# Loongson_Continuation.net
KiCad netlist of a schematic drawn in EasyEDA Pro
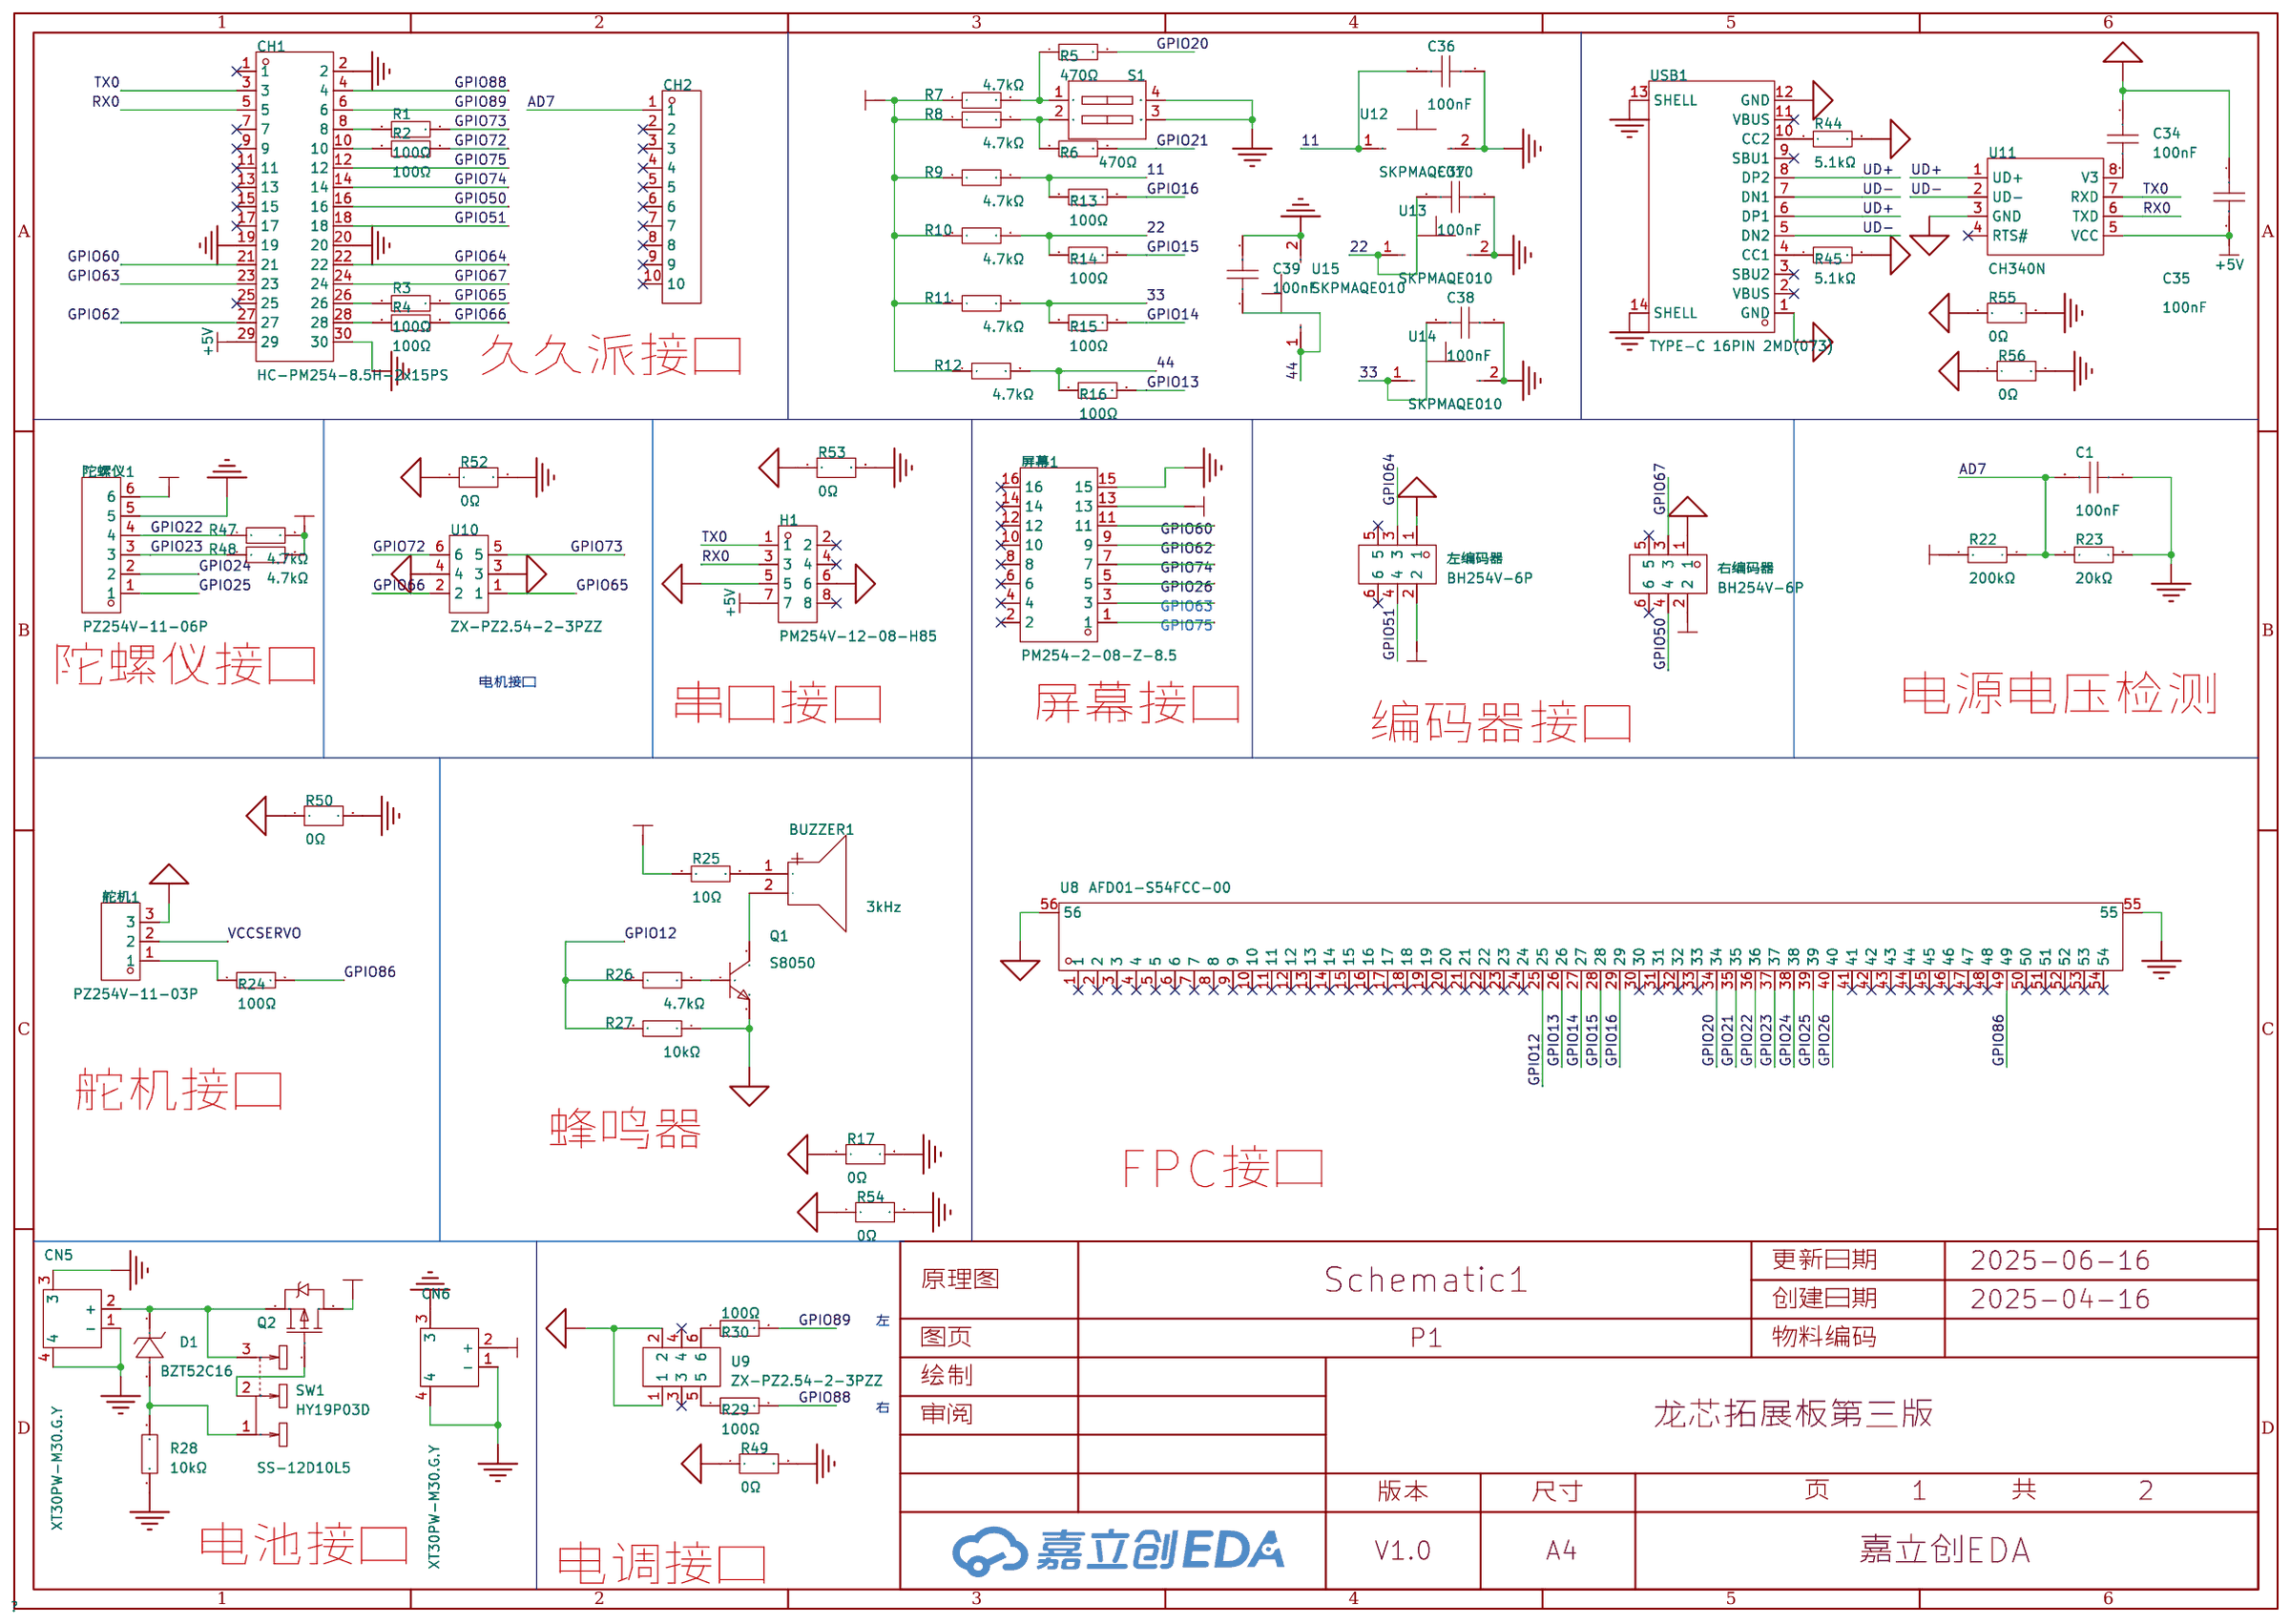
[diagram p0: P1]
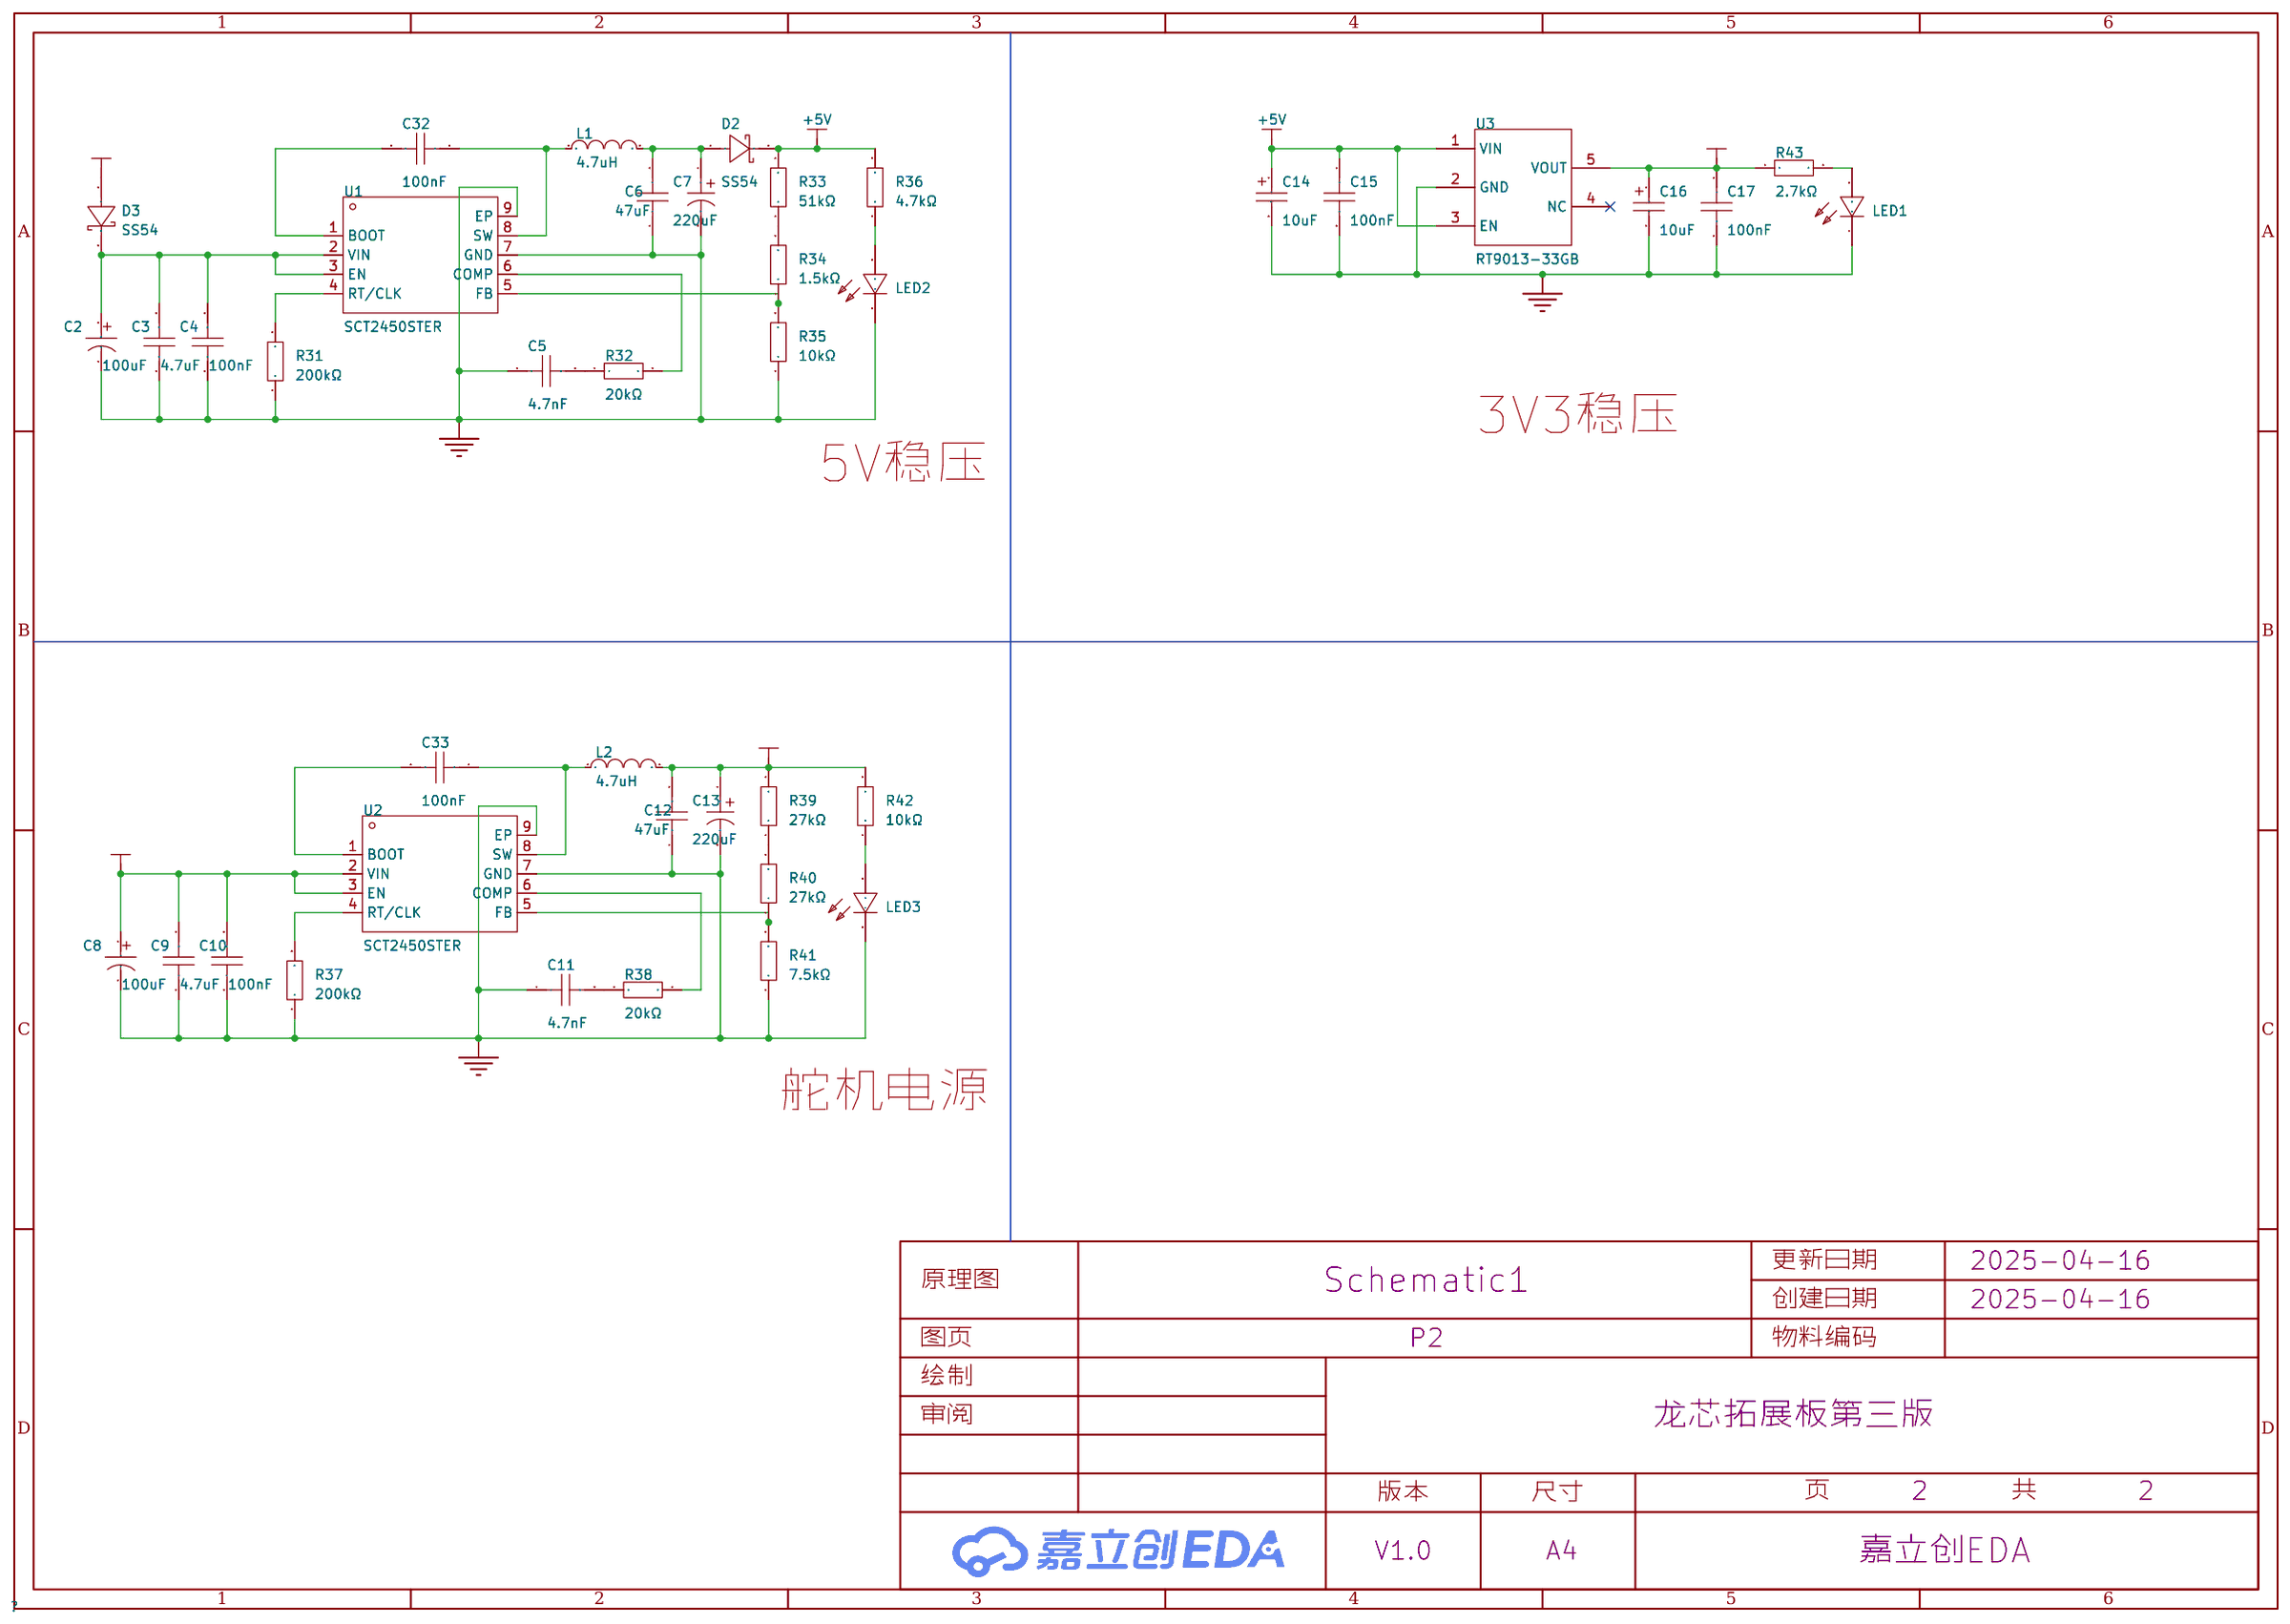
[diagram p1: P2]

(export (version "E")
  (design (tool "Eeschema 10.0.6"))
  (components
    (comp (ref "BUZZER1")
      (value "3kHz")
      (footprint "easyedapro:BUZ-TH_BD9.0-P5.00-D0.6-FD")
      (description "驱动方式:有源(内含驱动线路);构造类型:电磁式;频率:3kHz;声压(SPL):85dB;")
      (fields (field (name "Manufacturer Part") "HNB09A03") (field (name "Manufacturer") "华能"))
      (libsource (lib "easyedapro") (part "HNB09A03"))
    )
    (comp (ref "C1")
      (value "100nF")
      (footprint "easyedapro:C0603")
      (description "容值:100nF;精度:±10%;额定电压:50V;材质(温度系数):X7R;")
      (fields
        (field (name "Manufacturer Part") "CGA0603X7R104K500JT")
        (field (name "Manufacturer") "HRE(芯声)")
      )
      (libsource (lib "easyedapro") (part "CGA0603X7R104K500JT"))
    )
    (comp (ref "C34")
      (value "100nF")
      (footprint "easyedapro:C0603")
      (description "容值:100nF;精度:±10%;额定电压:50V;材质(温度系数):X7R;")
      (fields
        (field (name "Manufacturer Part") "CGA0603X7R104K500JT")
        (field (name "Manufacturer") "HRE(芯声)")
      )
      (libsource (lib "easyedapro") (part "CGA0603X7R104K500JT"))
    )
    (comp (ref "C35")
      (value "100nF")
      (footprint "easyedapro:C0603")
      (description "容值:100nF;精度:±10%;额定电压:50V;材质(温度系数):X7R;")
      (fields
        (field (name "Manufacturer Part") "CGA0603X7R104K500JT")
        (field (name "Manufacturer") "HRE(芯声)")
      )
      (libsource (lib "easyedapro") (part "CGA0603X7R104K500JT"))
    )
    (comp (ref "C36")
      (value "100nF")
      (footprint "easyedapro:C0603")
      (description "容值:100nF;精度:±10%;额定电压:50V;材质(温度系数):X7R;")
      (fields
        (field (name "Manufacturer Part") "CGA0603X7R104K500JT")
        (field (name "Manufacturer") "HRE(芯声)")
      )
      (libsource (lib "easyedapro") (part "CGA0603X7R104K500JT"))
    )
    (comp (ref "C37")
      (value "100nF")
      (footprint "easyedapro:C0603")
      (description "容值:100nF;精度:±10%;额定电压:50V;材质(温度系数):X7R;")
      (fields
        (field (name "Manufacturer Part") "CGA0603X7R104K500JT")
        (field (name "Manufacturer") "HRE(芯声)")
      )
      (libsource (lib "easyedapro") (part "CGA0603X7R104K500JT"))
    )
    (comp (ref "C38")
      (value "100nF")
      (footprint "easyedapro:C0603")
      (description "容值:100nF;精度:±10%;额定电压:50V;材质(温度系数):X7R;")
      (fields
        (field (name "Manufacturer Part") "CGA0603X7R104K500JT")
        (field (name "Manufacturer") "HRE(芯声)")
      )
      (libsource (lib "easyedapro") (part "CGA0603X7R104K500JT"))
    )
    (comp (ref "C39")
      (value "100nF")
      (footprint "easyedapro:C0603")
      (description "容值:100nF;精度:±10%;额定电压:50V;材质(温度系数):X7R;")
      (fields
        (field (name "Manufacturer Part") "CGA0603X7R104K500JT")
        (field (name "Manufacturer") "HRE(芯声)")
      )
      (libsource (lib "easyedapro") (part "CGA0603X7R104K500JT"))
    )
    (comp (ref "CH1")
      (value "HC-PM254-8.5H-2x15PS")
      (footprint "easyedapro:HDR-SMD_30P-P2.54-V-F-R2-C15-LS7.1-1")
      (fields (field (name "Manufacturer") "HC(虹成电子)"))
      (libsource (lib "easyedapro") (part "HC-PM254-8.5H-2X15PS"))
    )
    (comp (ref "CH2")
      (value "HX PM2.54-1x10P TP-YQ")
      (footprint "easyedapro:HDR-SMD_10P-P2.54-V-F-LS4.7_R2")
      (fields (field (name "Manufacturer") "hanxia(韩下)"))
      (libsource (lib "easyedapro") (part "HX PM2.54-1X10P TP-YQ"))
    )
    (comp (ref "CN5")
      (value "XT30PW-M30.G.Y")
      (footprint "easyedapro:CONN-TH_XT30PW-M")
      (description "类别:-;类型1:-;")
      (fields (field (name "Manufacturer") "AMASS(艾迈斯)"))
      (libsource (lib "easyedapro") (part "XT30PW-M"))
    )
    (comp (ref "CN6")
      (value "XT30PW-M30.G.Y")
      (footprint "easyedapro:CONN-TH_XT30PW-M")
      (description "类别:-;类型1:-;")
      (fields (field (name "Manufacturer") "AMASS(艾迈斯)"))
      (libsource (lib "easyedapro") (part "XT30PW-M"))
    )
    (comp (ref "D1")
      (value "BZT52C16")
      (footprint "easyedapro:SOD-123_L2.7-W1.6-LS3.7-RD")
      (description "二极管配置:独立式;稳压值(标称值):16V;稳压值(范围):15.2V~16.8V;耗散功率(Pd):500mW;")
      (fields (field (name "Manufacturer") "宏嘉诚"))
      (libsource (lib "easyedapro") (part "BZT52C16_C19077413"))
    )
    (comp (ref "H1")
      (value "PM254V-12-08-H85")
      (footprint "easyedapro:HDR-TH_8P-P2.54-V-F-R2-C4-S2.54")
      (fields (field (name "Manufacturer") "XFCN(兴飞)"))
      (libsource (lib "easyedapro") (part "PM254V-12-08-H85_C2834799"))
    )
    (comp (ref "Q1")
      (value "S8050")
      (footprint "easyedapro:SOT-23-3_L2.9-W1.6-P1.90-LS2.8-BR")
      (description "晶体管类型:NPN;集电极电流(Ic):500mA;集射极击穿电压(Vceo):25V;功率(Pd):300mW;")
      (fields (field (name "Manufacturer") "Hottech(合科泰)"))
      (libsource (lib "easyedapro") (part "S8050_C181158"))
    )
    (comp (ref "Q2")
      (value "HY19P03D")
      (footprint "easyedapro:TO-252-2_L6.6-W6.1-P4.57-LS9.9-TL-CW")
      (fields (field (name "Manufacturer") "HUAYI(华羿微)"))
      (libsource (lib "easyedapro") (part "HY19P03D"))
    )
    (comp (ref "R1")
      (value "100Ω")
      (footprint "easyedapro:R0603")
      (description "电阻类型:厚膜电阻;阻值:100Ω;精度:±1%;功率:100mW;最大工作电压:75V;温度系数:±200ppm/°C;")
      (fields
        (field (name "Manufacturer Part") "0603WAF1000T5E")
        (field (name "Manufacturer") "UNI-ROYAL(厚声)")
      )
      (libsource (lib "easyedapro") (part "0603WAF1000T5E"))
    )
    (comp (ref "R2")
      (value "100Ω")
      (footprint "easyedapro:R0603")
      (description "电阻类型:厚膜电阻;阻值:100Ω;精度:±1%;功率:100mW;最大工作电压:75V;温度系数:±200ppm/°C;")
      (fields
        (field (name "Manufacturer Part") "0603WAF1000T5E")
        (field (name "Manufacturer") "UNI-ROYAL(厚声)")
      )
      (libsource (lib "easyedapro") (part "0603WAF1000T5E"))
    )
    (comp (ref "R3")
      (value "100Ω")
      (footprint "easyedapro:R0603")
      (description "电阻类型:厚膜电阻;阻值:100Ω;精度:±1%;功率:100mW;最大工作电压:75V;温度系数:±200ppm/°C;")
      (fields
        (field (name "Manufacturer Part") "0603WAF1000T5E")
        (field (name "Manufacturer") "UNI-ROYAL(厚声)")
      )
      (libsource (lib "easyedapro") (part "0603WAF1000T5E"))
    )
    (comp (ref "R4")
      (value "100Ω")
      (footprint "easyedapro:R0603")
      (description "电阻类型:厚膜电阻;阻值:100Ω;精度:±1%;功率:100mW;最大工作电压:75V;温度系数:±200ppm/°C;")
      (fields
        (field (name "Manufacturer Part") "0603WAF1000T5E")
        (field (name "Manufacturer") "UNI-ROYAL(厚声)")
      )
      (libsource (lib "easyedapro") (part "0603WAF1000T5E"))
    )
    (comp (ref "R5")
      (value "470Ω")
      (footprint "easyedapro:R0603")
      (description "电阻类型:厚膜电阻;阻值:470Ω;精度:±1%;功率:100mW;最大工作电压:75V;温度系数:±100ppm/°C;")
      (fields
        (field (name "Manufacturer Part") "0603WAF4700T5E")
        (field (name "Manufacturer") "UNI-ROYAL(厚声)")
      )
      (libsource (lib "easyedapro") (part "0603WAF4700T5E"))
    )
    (comp (ref "R6")
      (value "470Ω")
      (footprint "easyedapro:R0603")
      (description "电阻类型:厚膜电阻;阻值:470Ω;精度:±1%;功率:100mW;最大工作电压:75V;温度系数:±100ppm/°C;")
      (fields
        (field (name "Manufacturer Part") "0603WAF4700T5E")
        (field (name "Manufacturer") "UNI-ROYAL(厚声)")
      )
      (libsource (lib "easyedapro") (part "0603WAF4700T5E"))
    )
    (comp (ref "R7")
      (value "4.7kΩ")
      (footprint "easyedapro:R0603")
      (description "电阻类型:厚膜电阻;阻值:4.7kΩ;精度:±1%;功率:100mW;最大工作电压:75V;温度系数:±100ppm/°C;")
      (fields
        (field (name "Manufacturer Part") "0603WAF4701T5E")
        (field (name "Manufacturer") "UNI-ROYAL(厚声)")
      )
      (libsource (lib "easyedapro") (part "0603WAF4701T5E"))
    )
    (comp (ref "R8")
      (value "4.7kΩ")
      (footprint "easyedapro:R0603")
      (description "电阻类型:厚膜电阻;阻值:4.7kΩ;精度:±1%;功率:100mW;最大工作电压:75V;温度系数:±100ppm/°C;")
      (fields
        (field (name "Manufacturer Part") "0603WAF4701T5E")
        (field (name "Manufacturer") "UNI-ROYAL(厚声)")
      )
      (libsource (lib "easyedapro") (part "0603WAF4701T5E"))
    )
    (comp (ref "R9")
      (value "4.7kΩ")
      (footprint "easyedapro:R0603")
      (description "电阻类型:厚膜电阻;阻值:4.7kΩ;精度:±1%;功率:100mW;最大工作电压:75V;温度系数:±100ppm/°C;")
      (fields
        (field (name "Manufacturer Part") "0603WAF4701T5E")
        (field (name "Manufacturer") "UNI-ROYAL(厚声)")
      )
      (libsource (lib "easyedapro") (part "0603WAF4701T5E"))
    )
    (comp (ref "R10")
      (value "4.7kΩ")
      (footprint "easyedapro:R0603")
      (description "电阻类型:厚膜电阻;阻值:4.7kΩ;精度:±1%;功率:100mW;最大工作电压:75V;温度系数:±100ppm/°C;")
      (fields
        (field (name "Manufacturer Part") "0603WAF4701T5E")
        (field (name "Manufacturer") "UNI-ROYAL(厚声)")
      )
      (libsource (lib "easyedapro") (part "0603WAF4701T5E"))
    )
    (comp (ref "R11")
      (value "4.7kΩ")
      (footprint "easyedapro:R0603")
      (description "电阻类型:厚膜电阻;阻值:4.7kΩ;精度:±1%;功率:100mW;最大工作电压:75V;温度系数:±100ppm/°C;")
      (fields
        (field (name "Manufacturer Part") "0603WAF4701T5E")
        (field (name "Manufacturer") "UNI-ROYAL(厚声)")
      )
      (libsource (lib "easyedapro") (part "0603WAF4701T5E"))
    )
    (comp (ref "R12")
      (value "4.7kΩ")
      (footprint "easyedapro:R0603")
      (description "电阻类型:厚膜电阻;阻值:4.7kΩ;精度:±1%;功率:100mW;最大工作电压:75V;温度系数:±100ppm/°C;")
      (fields
        (field (name "Manufacturer Part") "0603WAF4701T5E")
        (field (name "Manufacturer") "UNI-ROYAL(厚声)")
      )
      (libsource (lib "easyedapro") (part "0603WAF4701T5E"))
    )
    (comp (ref "R13")
      (value "100Ω")
      (footprint "easyedapro:R0603")
      (description "电阻类型:厚膜电阻;阻值:100Ω;精度:±1%;功率:100mW;最大工作电压:75V;温度系数:±200ppm/°C;")
      (fields
        (field (name "Manufacturer Part") "0603WAF1000T5E")
        (field (name "Manufacturer") "UNI-ROYAL(厚声)")
      )
      (libsource (lib "easyedapro") (part "0603WAF1000T5E"))
    )
    (comp (ref "R14")
      (value "100Ω")
      (footprint "easyedapro:R0603")
      (description "电阻类型:厚膜电阻;阻值:100Ω;精度:±1%;功率:100mW;最大工作电压:75V;温度系数:±200ppm/°C;")
      (fields
        (field (name "Manufacturer Part") "0603WAF1000T5E")
        (field (name "Manufacturer") "UNI-ROYAL(厚声)")
      )
      (libsource (lib "easyedapro") (part "0603WAF1000T5E"))
    )
    (comp (ref "R15")
      (value "100Ω")
      (footprint "easyedapro:R0603")
      (description "电阻类型:厚膜电阻;阻值:100Ω;精度:±1%;功率:100mW;最大工作电压:75V;温度系数:±200ppm/°C;")
      (fields
        (field (name "Manufacturer Part") "0603WAF1000T5E")
        (field (name "Manufacturer") "UNI-ROYAL(厚声)")
      )
      (libsource (lib "easyedapro") (part "0603WAF1000T5E"))
    )
    (comp (ref "R16")
      (value "100Ω")
      (footprint "easyedapro:R0603")
      (description "电阻类型:厚膜电阻;阻值:100Ω;精度:±1%;功率:100mW;最大工作电压:75V;温度系数:±200ppm/°C;")
      (fields
        (field (name "Manufacturer Part") "0603WAF1000T5E")
        (field (name "Manufacturer") "UNI-ROYAL(厚声)")
      )
      (libsource (lib "easyedapro") (part "0603WAF1000T5E"))
    )
    (comp (ref "R17")
      (value "0Ω")
      (footprint "easyedapro:R1206")
      (description "电阻类型:厚膜电阻;阻值:0Ω;精度:±5%;功率:250mW;最大工作电压:200V;")
      (fields (field (name "Manufacturer Part") "FRC1206P000 TS") (field (name "Manufacturer") "FOJAN(富捷)"))
      (libsource (lib "easyedapro") (part "FRC1206P000 TS"))
    )
    (comp (ref "R22")
      (value "200kΩ")
      (footprint "easyedapro:R0603")
      (description "电阻类型:厚膜电阻;阻值:200kΩ;精度:±1%;功率:100mW;最大工作电压:75V;温度系数:±100ppm/°C;")
      (fields
        (field (name "Manufacturer Part") "0603WAF2003T5E")
        (field (name "Manufacturer") "UNI-ROYAL(厚声)")
      )
      (libsource (lib "easyedapro") (part "0603WAF2003T5E"))
    )
    (comp (ref "R23")
      (value "20kΩ")
      (footprint "easyedapro:R0603")
      (description "电阻类型:厚膜电阻;阻值:20kΩ;精度:±1%;功率:100mW;最大工作电压:75V;温度系数:±100ppm/°C;")
      (fields
        (field (name "Manufacturer Part") "0603WAF2002T5E")
        (field (name "Manufacturer") "UNI-ROYAL(厚声)")
      )
      (libsource (lib "easyedapro") (part "0603WAF2002T5E"))
    )
    (comp (ref "R24")
      (value "100Ω")
      (footprint "easyedapro:R0603")
      (description "电阻类型:厚膜电阻;阻值:100Ω;精度:±1%;功率:100mW;最大工作电压:75V;温度系数:±200ppm/°C;")
      (fields
        (field (name "Manufacturer Part") "0603WAF1000T5E")
        (field (name "Manufacturer") "UNI-ROYAL(厚声)")
      )
      (libsource (lib "easyedapro") (part "0603WAF1000T5E"))
    )
    (comp (ref "R25")
      (value "10Ω")
      (footprint "easyedapro:R0603")
      (description "电阻类型:厚膜电阻;阻值:10Ω;精度:±1%;功率:100mW;最大工作电压:75V;温度系数:±400ppm/°C;")
      (fields
        (field (name "Manufacturer Part") "0603WAF100JT5E")
        (field (name "Manufacturer") "UNI-ROYAL(厚声)")
      )
      (libsource (lib "easyedapro") (part "0603WAF100JT5E"))
    )
    (comp (ref "R26")
      (value "4.7kΩ")
      (footprint "easyedapro:R0603")
      (description "电阻类型:厚膜电阻;阻值:4.7kΩ;精度:±1%;功率:100mW;最大工作电压:75V;温度系数:±100ppm/°C;")
      (fields
        (field (name "Manufacturer Part") "0603WAF4701T5E")
        (field (name "Manufacturer") "UNI-ROYAL(厚声)")
      )
      (libsource (lib "easyedapro") (part "0603WAF4701T5E"))
    )
    (comp (ref "R27")
      (value "10kΩ")
      (footprint "easyedapro:R0603")
      (description "电阻类型:厚膜电阻;阻值:10kΩ;精度:±1%;功率:100mW;最大工作电压:75V;温度系数:±100ppm/°C;")
      (fields
        (field (name "Manufacturer Part") "0603WAF1002T5E")
        (field (name "Manufacturer") "UNI-ROYAL(厚声)")
      )
      (libsource (lib "easyedapro") (part "0603WAF1002T5E"))
    )
    (comp (ref "R28")
      (value "10kΩ")
      (footprint "easyedapro:R0603")
      (description "电阻类型:厚膜电阻;阻值:10kΩ;精度:±1%;功率:100mW;最大工作电压:75V;温度系数:±100ppm/°C;")
      (fields
        (field (name "Manufacturer Part") "0603WAF1002T5E")
        (field (name "Manufacturer") "UNI-ROYAL(厚声)")
      )
      (libsource (lib "easyedapro") (part "0603WAF1002T5E"))
    )
    (comp (ref "R29")
      (value "100Ω")
      (footprint "easyedapro:R0603")
      (description "电阻类型:厚膜电阻;阻值:100Ω;精度:±1%;功率:100mW;最大工作电压:75V;温度系数:±200ppm/°C;")
      (fields
        (field (name "Manufacturer Part") "0603WAF1000T5E")
        (field (name "Manufacturer") "UNI-ROYAL(厚声)")
      )
      (libsource (lib "easyedapro") (part "0603WAF1000T5E"))
    )
    (comp (ref "R30")
      (value "100Ω")
      (footprint "easyedapro:R0603")
      (description "电阻类型:厚膜电阻;阻值:100Ω;精度:±1%;功率:100mW;最大工作电压:75V;温度系数:±200ppm/°C;")
      (fields
        (field (name "Manufacturer Part") "0603WAF1000T5E")
        (field (name "Manufacturer") "UNI-ROYAL(厚声)")
      )
      (libsource (lib "easyedapro") (part "0603WAF1000T5E"))
    )
    (comp (ref "R44")
      (value "5.1kΩ")
      (footprint "easyedapro:R0603")
      (description "电阻类型:厚膜电阻;阻值:5.1kΩ;精度:±1%;功率:100mW;最大工作电压:75V;温度系数:±100ppm/°C;")
      (fields
        (field (name "Manufacturer Part") "0603WAF5101T5E")
        (field (name "Manufacturer") "UNI-ROYAL(厚声)")
      )
      (libsource (lib "easyedapro") (part "0603WAF5101T5E"))
    )
    (comp (ref "R45")
      (value "5.1kΩ")
      (footprint "easyedapro:R0603")
      (description "电阻类型:厚膜电阻;阻值:5.1kΩ;精度:±1%;功率:100mW;最大工作电压:75V;温度系数:±100ppm/°C;")
      (fields
        (field (name "Manufacturer Part") "0603WAF5101T5E")
        (field (name "Manufacturer") "UNI-ROYAL(厚声)")
      )
      (libsource (lib "easyedapro") (part "0603WAF5101T5E"))
    )
    (comp (ref "R47")
      (value "4.7kΩ")
      (footprint "easyedapro:R0603")
      (description "电阻类型:厚膜电阻;阻值:4.7kΩ;精度:±1%;功率:100mW;最大工作电压:75V;温度系数:±100ppm/°C;")
      (fields
        (field (name "Manufacturer Part") "0603WAF4701T5E")
        (field (name "Manufacturer") "UNI-ROYAL(厚声)")
      )
      (libsource (lib "easyedapro") (part "0603WAF4701T5E"))
    )
    (comp (ref "R48")
      (value "4.7kΩ")
      (footprint "easyedapro:R0603")
      (description "电阻类型:厚膜电阻;阻值:4.7kΩ;精度:±1%;功率:100mW;最大工作电压:75V;温度系数:±100ppm/°C;")
      (fields
        (field (name "Manufacturer Part") "0603WAF4701T5E")
        (field (name "Manufacturer") "UNI-ROYAL(厚声)")
      )
      (libsource (lib "easyedapro") (part "0603WAF4701T5E"))
    )
    (comp (ref "R49")
      (value "0Ω")
      (footprint "easyedapro:R1206")
      (description "电阻类型:厚膜电阻;阻值:0Ω;精度:±5%;功率:250mW;最大工作电压:200V;")
      (fields (field (name "Manufacturer Part") "FRC1206P000 TS") (field (name "Manufacturer") "FOJAN(富捷)"))
      (libsource (lib "easyedapro") (part "FRC1206P000 TS"))
    )
    (comp (ref "R50")
      (value "0Ω")
      (footprint "easyedapro:R1206")
      (description "电阻类型:厚膜电阻;阻值:0Ω;精度:±5%;功率:250mW;最大工作电压:200V;")
      (fields (field (name "Manufacturer Part") "FRC1206P000 TS") (field (name "Manufacturer") "FOJAN(富捷)"))
      (libsource (lib "easyedapro") (part "FRC1206P000 TS"))
    )
    (comp (ref "R52")
      (value "0Ω")
      (footprint "easyedapro:R1206")
      (description "电阻类型:厚膜电阻;阻值:0Ω;精度:±5%;功率:250mW;最大工作电压:200V;")
      (fields (field (name "Manufacturer Part") "FRC1206P000 TS") (field (name "Manufacturer") "FOJAN(富捷)"))
      (libsource (lib "easyedapro") (part "FRC1206P000 TS"))
    )
    (comp (ref "R53")
      (value "0Ω")
      (footprint "easyedapro:R1206")
      (description "电阻类型:厚膜电阻;阻值:0Ω;精度:±5%;功率:250mW;最大工作电压:200V;")
      (fields (field (name "Manufacturer Part") "FRC1206P000 TS") (field (name "Manufacturer") "FOJAN(富捷)"))
      (libsource (lib "easyedapro") (part "FRC1206P000 TS"))
    )
    (comp (ref "R54")
      (value "0Ω")
      (footprint "easyedapro:R1206")
      (description "电阻类型:厚膜电阻;阻值:0Ω;精度:±5%;功率:250mW;最大工作电压:200V;")
      (fields (field (name "Manufacturer Part") "FRC1206P000 TS") (field (name "Manufacturer") "FOJAN(富捷)"))
      (libsource (lib "easyedapro") (part "FRC1206P000 TS"))
    )
    (comp (ref "R55")
      (value "0Ω")
      (footprint "easyedapro:R1206")
      (description "电阻类型:厚膜电阻;阻值:0Ω;精度:±5%;功率:250mW;最大工作电压:200V;")
      (fields (field (name "Manufacturer Part") "FRC1206P000 TS") (field (name "Manufacturer") "FOJAN(富捷)"))
      (libsource (lib "easyedapro") (part "FRC1206P000 TS"))
    )
    (comp (ref "R56")
      (value "0Ω")
      (footprint "easyedapro:R1206")
      (description "电阻类型:厚膜电阻;阻值:0Ω;精度:±5%;功率:250mW;最大工作电压:200V;")
      (fields (field (name "Manufacturer Part") "FRC1206P000 TS") (field (name "Manufacturer") "FOJAN(富捷)"))
      (libsource (lib "easyedapro") (part "FRC1206P000 TS"))
    )
    (comp (ref "S1")
      (value "DSIC02LS-P")
      (footprint "easyedapro:SW-SMD_4P-L5.1-W6.1-P2.54-LS9.8")
      (description "类型:平拨,凸起式;电路结构:单刀单掷;开关位数:2位;额定电流:25mA;额定电压:24V;使用寿命:3千次;颜色:黑色;")
      (fields (field (name "Manufacturer") "XKB Connectivity(中国星坤)"))
      (libsource (lib "easyedapro") (part "DSIC02LS-P_C489174"))
    )
    (comp (ref "SW1")
      (value "SS-12D10L5")
      (footprint "easyedapro:SW-TH_SS-12D10L5")
      (description "电路结构:单刀双掷;安装方式:直插;开关颜色:黑色;额定电流(DC):3A;额定电压(DC):125V;额定电流(AC):3A;额定电压(AC):125V;机械寿命:1万次;")
      (fields (field (name "Manufacturer") "XKB Connectivity(中国星坤)"))
      (libsource (lib "easyedapro") (part "SS-12D10L5"))
    )
    (comp (ref "U8")
      (value "AFD01-S54FCC-00")
      (footprint "easyedapro:FPC-SMD_54P-P0.50_AFD01-S54FCA-00")
      (description "锁定特性:翻盖式;触点类型:下接;触点数量:54P;间距:0.5mm;安装类型:卧贴;")
      (fields (field (name "Manufacturer") "JS(钜硕电子)"))
      (libsource (lib "easyedapro") (part "AFD01-S54FCC-00"))
    )
    (comp (ref "U9")
      (value "ZX-PZ2.54-2-3PZZ")
      (footprint "easyedapro:HDR-TH_6P-P2.54-V-M-R2-C3-S2.54-1")
      (fields (field (name "Manufacturer") "Megastar(兆星)"))
      (libsource (lib "easyedapro") (part "ZX-PZ2.54-2-3PZZ"))
    )
    (comp (ref "U10")
      (value "ZX-PZ2.54-2-3PZZ")
      (footprint "easyedapro:HDR-TH_6P-P2.54-V-M-R2-C3-S2.54-1")
      (fields (field (name "Manufacturer") "Megastar(兆星)"))
      (libsource (lib "easyedapro") (part "ZX-PZ2.54-2-3PZZ"))
    )
    (comp (ref "U11")
      (value "CH340N")
      (footprint "easyedapro:SOP-8_L4.9-W3.9-P1.27-LS6.0-BL")
      (description "应用功能:USB转串口;接口协议:USB 2.0;通道数:1;数据速率:2Mbps;")
      (fields (field (name "Manufacturer") "WCH(南京沁恒)"))
      (libsource (lib "easyedapro") (part "CH340N_C2977777"))
    )
    (comp (ref "U12")
      (value "SKPMAQE010")
      (footprint "easyedapro:KEY-SMD_2P-L6.0-W6.0-P6.00")
      (fields (field (name "Manufacturer") "ALPSALPINE(阿尔卑斯阿尔派)"))
      (libsource (lib "easyedapro") (part "SKPMAQE010"))
    )
    (comp (ref "U13")
      (value "SKPMAQE010")
      (footprint "easyedapro:KEY-SMD_2P-L6.0-W6.0-P6.00")
      (fields (field (name "Manufacturer") "ALPSALPINE(阿尔卑斯阿尔派)"))
      (libsource (lib "easyedapro") (part "SKPMAQE010"))
    )
    (comp (ref "U14")
      (value "SKPMAQE010")
      (footprint "easyedapro:KEY-SMD_2P-L6.0-W6.0-P6.00")
      (fields (field (name "Manufacturer") "ALPSALPINE(阿尔卑斯阿尔派)"))
      (libsource (lib "easyedapro") (part "SKPMAQE010"))
    )
    (comp (ref "U15")
      (value "SKPMAQE010")
      (footprint "easyedapro:KEY-SMD_2P-L6.0-W6.0-P6.00")
      (fields (field (name "Manufacturer") "ALPSALPINE(阿尔卑斯阿尔派)"))
      (libsource (lib "easyedapro") (part "SKPMAQE010"))
    )
    (comp (ref "USB1")
      (value "TYPE-C 16PIN 2MD(073)")
      (footprint "easyedapro:USB-C-SMD_TYPE-C-6PIN-2MD-073")
      (description "连接器类型:Type-C;标准:USB 3.1;公母:母;安装方式:卧贴;触点数量:16P;端口数量:1;额定电流 - 电源:5A;工作温度范围:-25°C~+85°C;")
      (fields (field (name "Manufacturer") "SHOU HAN(首韩)"))
      (libsource (lib "easyedapro") (part "TYPE-C 16PIN 2MD(073)"))
    )
    (comp (ref "右编码器")
      (value "BH254V-6P")
      (footprint "easyedapro:IDC-TH_6P-P2.54-V-R2-C3-S2.54")
      (description "连接器类型:简牛座;间距:2.54mm;结构:2x3P;额定电流:3A;额定电压:250V;封装形式:直插;行距:2.54mm;排数:2;每排PIN数:3;工作温度范围:-40°C~+105°C;")
      (fields (field (name "Manufacturer") "XFCN(兴飞)"))
      (libsource (lib "easyedapro") (part "BH254V-6P"))
    )
    (comp (ref "屏幕1")
      (value "PM254-2-08-Z-8.5")
      (footprint "easyedapro:HDR-TH_16P-P2.54-V-F-R2-C8-S2.54")
      (fields (field (name "Manufacturer") "HCTL(华灿天禄)"))
      (libsource (lib "easyedapro") (part "PM254-2-08-Z-8.5"))
    )
    (comp (ref "左编码器")
      (value "BH254V-6P")
      (footprint "easyedapro:IDC-TH_6P-P2.54-V-R2-C3-S2.54")
      (description "连接器类型:简牛座;间距:2.54mm;结构:2x3P;额定电流:3A;额定电压:250V;封装形式:直插;行距:2.54mm;排数:2;每排PIN数:3;工作温度范围:-40°C~+105°C;")
      (fields (field (name "Manufacturer") "XFCN(兴飞)"))
      (libsource (lib "easyedapro") (part "BH254V-6P"))
    )
    (comp (ref "舵机1")
      (value "PZ254V-11-03P")
      (footprint "easyedapro:HDR-TH_3P-P2.54-V-M")
      (fields (field (name "Manufacturer") "XFCN(兴飞)"))
      (libsource (lib "easyedapro") (part "PZ254V-11-03P_C2937625"))
    )
    (comp (ref "陀螺仪1")
      (value "PZ254V-11-06P")
      (footprint "easyedapro:HDR-TH_6P-P2.54-V-M")
      (fields (field (name "Manufacturer") "XFCN(兴飞)"))
      (libsource (lib "easyedapro") (part "PZ254V-11-06P"))
    )
    (comp (ref "C2")
      (value "100uF")
      (footprint "easyedapro:CAP-SMD_BD6.3-L6.6-W6.6-LS7.6-FD")
      (description "容值:100uF;精度:±20%;额定电压:35V;纹波电流:69mA@120Hz;等效串联电阻(ESR):-;")
      (fields (field (name "Manufacturer Part") "RVT1V101M0607") (field (name "Manufacturer") "ROQANG(容强)"))
      (libsource (lib "easyedapro") (part "RVT1V101M0607"))
    )
    (comp (ref "C3")
      (value "4.7uF")
      (footprint "easyedapro:C1206")
      (description "容值:4.7uF;精度:±10%;额定电压:35V;材质(温度系数):X5R;")
      (fields
        (field (name "Manufacturer Part") "CGA1206X5R475K350NT")
        (field (name "Manufacturer") "HRE(芯声)")
      )
      (libsource (lib "easyedapro") (part "CGA1206X5R475K350NT"))
    )
    (comp (ref "C4")
      (value "100nF")
      (footprint "easyedapro:C0603")
      (description "容值:100nF;精度:±10%;额定电压:50V;材质(温度系数):X7R;")
      (fields
        (field (name "Manufacturer Part") "CGA0603X7R104K500JT")
        (field (name "Manufacturer") "HRE(芯声)")
      )
      (libsource (lib "easyedapro") (part "CGA0603X7R104K500JT"))
    )
    (comp (ref "C5")
      (value "4.7nF")
      (footprint "easyedapro:C0603")
      (description "容值:4.7nF;精度:±10%;额定电压:50V;材质(温度系数):X7R;")
      (fields
        (field (name "Manufacturer Part") "CGA0603X7R472K500JT")
        (field (name "Manufacturer") "HRE(芯声)")
      )
      (libsource (lib "easyedapro") (part "CGA0603X7R472K500JT"))
    )
    (comp (ref "C6")
      (value "47uF")
      (footprint "easyedapro:C1206")
      (description "容值:47uF;精度:±20%;额定电压:25V;材质(温度系数):X5R;")
      (fields
        (field (name "Manufacturer Part") "CGA1206X5R476M250NT")
        (field (name "Manufacturer") "HRE(芯声)")
      )
      (libsource (lib "easyedapro") (part "CGA1206X5R476M250NT"))
    )
    (comp (ref "C7")
      (value "220uF")
      (footprint "easyedapro:CAP-SMD_BD6.3-L6.6-W6.6-LS7.4-FD")
      (description "容值:220uF;精度:±20%;额定电压:25V;纹波电流:150mA@120Hz;等效串联电阻(ESR):-;")
      (fields (field (name "Manufacturer Part") "RVT1E221M0607") (field (name "Manufacturer") "ROQANG(容强)"))
      (libsource (lib "easyedapro") (part "RVT1E221M0607_C2918361"))
    )
    (comp (ref "C8")
      (value "100uF")
      (footprint "easyedapro:CAP-SMD_BD6.3-L6.6-W6.6-LS7.6-FD")
      (description "容值:100uF;精度:±20%;额定电压:35V;纹波电流:69mA@120Hz;等效串联电阻(ESR):-;")
      (fields (field (name "Manufacturer Part") "RVT1V101M0607") (field (name "Manufacturer") "ROQANG(容强)"))
      (libsource (lib "easyedapro") (part "RVT1V101M0607"))
    )
    (comp (ref "C9")
      (value "4.7uF")
      (footprint "easyedapro:C1206")
      (description "容值:4.7uF;精度:±10%;额定电压:35V;材质(温度系数):X5R;")
      (fields
        (field (name "Manufacturer Part") "CGA1206X5R475K350NT")
        (field (name "Manufacturer") "HRE(芯声)")
      )
      (libsource (lib "easyedapro") (part "CGA1206X5R475K350NT"))
    )
    (comp (ref "C10")
      (value "100nF")
      (footprint "easyedapro:C0603")
      (description "容值:100nF;精度:±10%;额定电压:50V;材质(温度系数):X7R;")
      (fields
        (field (name "Manufacturer Part") "CGA0603X7R104K500JT")
        (field (name "Manufacturer") "HRE(芯声)")
      )
      (libsource (lib "easyedapro") (part "CGA0603X7R104K500JT"))
    )
    (comp (ref "C11")
      (value "4.7nF")
      (footprint "easyedapro:C0603")
      (description "容值:4.7nF;精度:±10%;额定电压:50V;材质(温度系数):X7R;")
      (fields
        (field (name "Manufacturer Part") "CGA0603X7R472K500JT")
        (field (name "Manufacturer") "HRE(芯声)")
      )
      (libsource (lib "easyedapro") (part "CGA0603X7R472K500JT"))
    )
    (comp (ref "C12")
      (value "47uF")
      (footprint "easyedapro:C1206")
      (description "容值:47uF;精度:±20%;额定电压:25V;材质(温度系数):X5R;")
      (fields
        (field (name "Manufacturer Part") "CGA1206X5R476M250NT")
        (field (name "Manufacturer") "HRE(芯声)")
      )
      (libsource (lib "easyedapro") (part "CGA1206X5R476M250NT"))
    )
    (comp (ref "C13")
      (value "220uF")
      (footprint "easyedapro:CAP-SMD_BD6.3-L6.6-W6.6-LS7.4-FD")
      (description "容值:220uF;精度:±20%;额定电压:25V;纹波电流:150mA@120Hz;等效串联电阻(ESR):-;")
      (fields (field (name "Manufacturer Part") "RVT1E221M0607") (field (name "Manufacturer") "ROQANG(容强)"))
      (libsource (lib "easyedapro") (part "RVT1E221M0607_C2918361"))
    )
    (comp (ref "C14")
      (value "10uF")
      (footprint "easyedapro:CAP-SMD_L3.2-W1.6-RD-C7171")
      (description "容值:10uF;精度:±10%;额定电压:16V;等效串联电阻:3Ω@100kHz;")
      (fields (field (name "Manufacturer Part") "TAJA106K016RNJ") (field (name "Manufacturer") "Kyocera AVX"))
      (libsource (lib "easyedapro") (part "TAJA106K016RNJ"))
    )
    (comp (ref "C15")
      (value "100nF")
      (footprint "easyedapro:C0603")
      (description "容值:100nF;精度:±10%;额定电压:50V;材质(温度系数):X7R;")
      (fields
        (field (name "Manufacturer Part") "CGA0603X7R104K500JT")
        (field (name "Manufacturer") "HRE(芯声)")
      )
      (libsource (lib "easyedapro") (part "CGA0603X7R104K500JT"))
    )
    (comp (ref "C16")
      (value "10uF")
      (footprint "easyedapro:CAP-SMD_L3.2-W1.6-RD-C7171")
      (description "容值:10uF;精度:±10%;额定电压:16V;等效串联电阻:3Ω@100kHz;")
      (fields (field (name "Manufacturer Part") "TAJA106K016RNJ") (field (name "Manufacturer") "Kyocera AVX"))
      (libsource (lib "easyedapro") (part "TAJA106K016RNJ"))
    )
    (comp (ref "C17")
      (value "100nF")
      (footprint "easyedapro:C0603")
      (description "容值:100nF;精度:±10%;额定电压:50V;材质(温度系数):X7R;")
      (fields
        (field (name "Manufacturer Part") "CGA0603X7R104K500JT")
        (field (name "Manufacturer") "HRE(芯声)")
      )
      (libsource (lib "easyedapro") (part "CGA0603X7R104K500JT"))
    )
    (comp (ref "C32")
      (value "100nF")
      (footprint "easyedapro:C0603")
      (description "容值:100nF;精度:±10%;额定电压:50V;材质(温度系数):X7R;")
      (fields
        (field (name "Manufacturer Part") "CGA0603X7R104K500JT")
        (field (name "Manufacturer") "HRE(芯声)")
      )
      (libsource (lib "easyedapro") (part "CGA0603X7R104K500JT"))
    )
    (comp (ref "C33")
      (value "100nF")
      (footprint "easyedapro:C0603")
      (description "容值:100nF;精度:±10%;额定电压:50V;材质(温度系数):X7R;")
      (fields
        (field (name "Manufacturer Part") "CGA0603X7R104K500JT")
        (field (name "Manufacturer") "HRE(芯声)")
      )
      (libsource (lib "easyedapro") (part "CGA0603X7R104K500JT"))
    )
    (comp (ref "D2")
      (value "SS54")
      (footprint "easyedapro:SMA_L4.3-W2.6-LS5.0-FD")
      (description "二极管配置:独立式;正向压降(Vf):550mV@5.0A;直流反向耐压(Vr):40V;整流电流:5A;")
      (fields (field (name "Manufacturer") "宏迦橙"))
      (libsource (lib "easyedapro") (part "SS54_C7420369"))
    )
    (comp (ref "D3")
      (value "SS54")
      (footprint "easyedapro:SMA_L4.3-W2.6-LS5.0-FD")
      (description "二极管配置:独立式;正向压降(Vf):550mV@5.0A;直流反向耐压(Vr):40V;整流电流:5A;")
      (fields (field (name "Manufacturer") "宏迦橙"))
      (libsource (lib "easyedapro") (part "SS54_C7420369"))
    )
    (comp (ref "L1")
      (value "4.7uH")
      (footprint "easyedapro:IND-SMD_L5.4-W5.2_FXL0530")
      (description "电感值:4.7uH;精度:±20%;额定电流:4.5A;饱和电流(Isat):5A;类型:一体成型电感;")
      (fields (field (name "Manufacturer Part") "FXL0530-4R7-M") (field (name "Manufacturer") "cjiang(长江微电)"))
      (libsource (lib "easyedapro") (part "FXL0530-4R7-M"))
    )
    (comp (ref "L2")
      (value "4.7uH")
      (footprint "easyedapro:IND-SMD_L5.4-W5.2_FXL0530")
      (description "电感值:4.7uH;精度:±20%;额定电流:4.5A;饱和电流(Isat):5A;类型:一体成型电感;")
      (fields (field (name "Manufacturer Part") "FXL0530-4R7-M") (field (name "Manufacturer") "cjiang(长江微电)"))
      (libsource (lib "easyedapro") (part "FXL0530-4R7-M"))
    )
    (comp (ref "LED1")
      (value "NCD0603R1")
      (footprint "easyedapro:LED0603-RD_RED")
      (fields (field (name "Manufacturer") "国星光电"))
      (libsource (lib "easyedapro") (part "FC-DA1608HRK-620D"))
    )
    (comp (ref "LED2")
      (value "NCD0603R1")
      (footprint "easyedapro:LED0603-RD_RED")
      (fields (field (name "Manufacturer") "国星光电"))
      (libsource (lib "easyedapro") (part "FC-DA1608HRK-620D"))
    )
    (comp (ref "LED3")
      (value "NCD0603B1")
      (footprint "easyedapro:LED0603-RD")
      (fields (field (name "Manufacturer") "国星光电"))
      (libsource (lib "easyedapro") (part "FC-DA1608BK-470H10"))
    )
    (comp (ref "R31")
      (value "200kΩ")
      (footprint "easyedapro:R0603")
      (description "电阻类型:厚膜电阻;阻值:200kΩ;精度:±1%;功率:100mW;最大工作电压:75V;温度系数:±100ppm/°C;")
      (fields
        (field (name "Manufacturer Part") "0603WAF2003T5E")
        (field (name "Manufacturer") "UNI-ROYAL(厚声)")
      )
      (libsource (lib "easyedapro") (part "0603WAF2003T5E"))
    )
    (comp (ref "R32")
      (value "20kΩ")
      (footprint "easyedapro:R0603")
      (description "电阻类型:厚膜电阻;阻值:20kΩ;精度:±1%;功率:100mW;最大工作电压:75V;温度系数:±100ppm/°C;")
      (fields
        (field (name "Manufacturer Part") "0603WAF2002T5E")
        (field (name "Manufacturer") "UNI-ROYAL(厚声)")
      )
      (libsource (lib "easyedapro") (part "0603WAF2002T5E"))
    )
    (comp (ref "R33")
      (value "51kΩ")
      (footprint "easyedapro:R0603")
      (description "电阻类型:厚膜电阻;阻值:51kΩ;精度:±1%;功率:100mW;最大工作电压:75V;温度系数:±100ppm/°C;")
      (fields
        (field (name "Manufacturer Part") "0603WAF5102T5E")
        (field (name "Manufacturer") "UNI-ROYAL(厚声)")
      )
      (libsource (lib "easyedapro") (part "0603WAF5102T5E"))
    )
    (comp (ref "R34")
      (value "1.5kΩ")
      (footprint "easyedapro:R0603")
      (description "电阻类型:厚膜电阻;阻值:1.5kΩ;精度:±1%;功率:100mW;最大工作电压:75V;温度系数:±100ppm/°C;")
      (fields
        (field (name "Manufacturer Part") "0603WAF1501T5E")
        (field (name "Manufacturer") "UNI-ROYAL(厚声)")
      )
      (libsource (lib "easyedapro") (part "0603WAF1501T5E"))
    )
    (comp (ref "R35")
      (value "10kΩ")
      (footprint "easyedapro:R0603")
      (description "电阻类型:厚膜电阻;阻值:10kΩ;精度:±1%;功率:100mW;最大工作电压:75V;温度系数:±100ppm/°C;")
      (fields
        (field (name "Manufacturer Part") "0603WAF1002T5E")
        (field (name "Manufacturer") "UNI-ROYAL(厚声)")
      )
      (libsource (lib "easyedapro") (part "0603WAF1002T5E"))
    )
    (comp (ref "R36")
      (value "4.7kΩ")
      (footprint "easyedapro:R0603")
      (description "电阻类型:厚膜电阻;阻值:4.7kΩ;精度:±1%;功率:100mW;最大工作电压:75V;温度系数:±100ppm/°C;")
      (fields
        (field (name "Manufacturer Part") "0603WAF4701T5E")
        (field (name "Manufacturer") "UNI-ROYAL(厚声)")
      )
      (libsource (lib "easyedapro") (part "0603WAF4701T5E"))
    )
    (comp (ref "R37")
      (value "200kΩ")
      (footprint "easyedapro:R0603")
      (description "电阻类型:厚膜电阻;阻值:200kΩ;精度:±1%;功率:100mW;最大工作电压:75V;温度系数:±100ppm/°C;")
      (fields
        (field (name "Manufacturer Part") "0603WAF2003T5E")
        (field (name "Manufacturer") "UNI-ROYAL(厚声)")
      )
      (libsource (lib "easyedapro") (part "0603WAF2003T5E"))
    )
    (comp (ref "R38")
      (value "20kΩ")
      (footprint "easyedapro:R0603")
      (description "电阻类型:厚膜电阻;阻值:20kΩ;精度:±1%;功率:100mW;最大工作电压:75V;温度系数:±100ppm/°C;")
      (fields
        (field (name "Manufacturer Part") "0603WAF2002T5E")
        (field (name "Manufacturer") "UNI-ROYAL(厚声)")
      )
      (libsource (lib "easyedapro") (part "0603WAF2002T5E"))
    )
    (comp (ref "R39")
      (value "27kΩ")
      (footprint "easyedapro:R0603")
      (description "电阻类型:厚膜电阻;阻值:27kΩ;精度:±1%;功率:100mW;最大工作电压:75V;温度系数:±100ppm/°C;")
      (fields
        (field (name "Manufacturer Part") "0603WAF2702T5E")
        (field (name "Manufacturer") "UNI-ROYAL(厚声)")
      )
      (libsource (lib "easyedapro") (part "0603WAF2702T5E"))
    )
    (comp (ref "R40")
      (value "27kΩ")
      (footprint "easyedapro:R0603")
      (description "电阻类型:厚膜电阻;阻值:27kΩ;精度:±1%;功率:100mW;最大工作电压:75V;温度系数:±100ppm/°C;")
      (fields
        (field (name "Manufacturer Part") "0603WAF2702T5E")
        (field (name "Manufacturer") "UNI-ROYAL(厚声)")
      )
      (libsource (lib "easyedapro") (part "0603WAF2702T5E"))
    )
    (comp (ref "R41")
      (value "7.5kΩ")
      (footprint "easyedapro:R0603")
      (description "电阻类型:厚膜电阻;阻值:7.5kΩ;精度:±1%;功率:100mW;最大工作电压:75V;温度系数:±100ppm/°C;")
      (fields
        (field (name "Manufacturer Part") "0603WAF7501T5E")
        (field (name "Manufacturer") "UNI-ROYAL(厚声)")
      )
      (libsource (lib "easyedapro") (part "0603WAF7501T5E"))
    )
    (comp (ref "R42")
      (value "10kΩ")
      (footprint "easyedapro:R0603")
      (description "电阻类型:厚膜电阻;阻值:10kΩ;精度:±1%;功率:100mW;最大工作电压:75V;温度系数:±100ppm/°C;")
      (fields
        (field (name "Manufacturer Part") "0603WAF1002T5E")
        (field (name "Manufacturer") "UNI-ROYAL(厚声)")
      )
      (libsource (lib "easyedapro") (part "0603WAF1002T5E"))
    )
    (comp (ref "R43")
      (value "2.7kΩ")
      (footprint "easyedapro:R0603")
      (description "电阻类型:厚膜电阻;阻值:2.7kΩ;精度:±1%;功率:100mW;最大工作电压:75V;温度系数:±100ppm/°C;")
      (fields
        (field (name "Manufacturer Part") "0603WAF2701T5E")
        (field (name "Manufacturer") "UNI-ROYAL(厚声)")
      )
      (libsource (lib "easyedapro") (part "0603WAF2701T5E"))
    )
    (comp (ref "U1")
      (value "SCT2450STER")
      (footprint "easyedapro:ESOP-8_L4.9-W3.9-P1.27-LS6.0-BL-EP")
      (description "功能类型:降压型;工作电压:3.8V~36V;输出电流:5A;")
      (fields (field (name "Manufacturer") "SCT(芯洲科技)"))
      (libsource (lib "easyedapro") (part "SCT2450STER"))
    )
    (comp (ref "U2")
      (value "SCT2450STER")
      (footprint "easyedapro:ESOP-8_L4.9-W3.9-P1.27-LS6.0-BL-EP")
      (description "功能类型:降压型;工作电压:3.8V~36V;输出电流:5A;")
      (fields (field (name "Manufacturer") "SCT(芯洲科技)"))
      (libsource (lib "easyedapro") (part "SCT2450STER"))
    )
    (comp (ref "U3")
      (value "RT9013-33GB")
      (footprint "easyedapro:SOT-23-5_L3.0-W1.7-P0.95-LS2.8-BL")
      (description "输出类型:固定;最大输入电压:5.5V;输出电压:3.3V;输出电流:500mA;电源纹波抑制比(PSRR):50dB@(10kHz);输出极性:正极;")
      (fields (field (name "Manufacturer") "RICHTEK(立锜)"))
      (libsource (lib "easyedapro") (part "RT9013-33GB"))
    )
  )
  (nets
    (net (code "1") (name "+5V") (class "Default")
      (node (ref "C14") (pin "1") (pinfunction "1_1") (pintype "input"))
      (node (ref "C15") (pin "1") (pinfunction "1_1") (pintype "unspecified"))
      (node (ref "C35") (pin "2") (pinfunction "2_2") (pintype "unspecified"))
      (node (ref "CH1") (pin "29") (pinfunction "29_29") (pintype "unspecified"))
      (node (ref "D2") (pin "2") (pinfunction "K_2") (pintype "unspecified"))
      (node (ref "H1") (pin "7") (pinfunction "7_7") (pintype "unspecified"))
      (node (ref "R33") (pin "2") (pinfunction "2_2") (pintype "input"))
      (node (ref "R36") (pin "2") (pinfunction "2_2") (pintype "input"))
      (node (ref "U11") (pin "5") (pinfunction "VCC_5") (pintype "unspecified"))
      (node (ref "U3") (pin "1") (pinfunction "VIN_1") (pintype "unspecified"))
      (node (ref "U3") (pin "3") (pinfunction "EN_3") (pintype "unspecified"))
    )
    (net (code "2") (name "3V3") (class "Default")
      (node (ref "C16") (pin "1") (pinfunction "1_1") (pintype "input"))
      (node (ref "C17") (pin "1") (pinfunction "1_1") (pintype "unspecified"))
      (node (ref "R10") (pin "1") (pinfunction "1_1") (pintype "input"))
      (node (ref "R11") (pin "1") (pinfunction "1_1") (pintype "input"))
      (node (ref "R12") (pin "1") (pinfunction "1_1") (pintype "input"))
      (node (ref "R25") (pin "1") (pinfunction "1_1") (pintype "input"))
      (node (ref "R43") (pin "1") (pinfunction "1_1") (pintype "input"))
      (node (ref "R47") (pin "2") (pinfunction "2_2") (pintype "input"))
      (node (ref "R48") (pin "2") (pinfunction "2_2") (pintype "input"))
      (node (ref "R7") (pin "1") (pinfunction "1_1") (pintype "input"))
      (node (ref "R8") (pin "1") (pinfunction "1_1") (pintype "input"))
      (node (ref "R9") (pin "1") (pinfunction "1_1") (pintype "input"))
      (node (ref "U3") (pin "5") (pinfunction "VOUT_5") (pintype "unspecified"))
      (node (ref "右编码器") (pin "2") (pinfunction "2_2") (pintype "unspecified"))
      (node (ref "屏幕1") (pin "13") (pinfunction "13_13") (pintype "unspecified"))
      (node (ref "左编码器") (pin "2") (pinfunction "2_2") (pintype "unspecified"))
      (node (ref "陀螺仪1") (pin "6") (pinfunction "6_6") (pintype "unspecified"))
    )
    (net (code "3") (name "11") (class "Default")
      (node (ref "C36") (pin "1") (pinfunction "1_1") (pintype "unspecified"))
      (node (ref "R13") (pin "1") (pinfunction "1_1") (pintype "input"))
      (node (ref "R9") (pin "2") (pinfunction "2_2") (pintype "input"))
      (node (ref "U12") (pin "1") (pinfunction "1_1") (pintype "input"))
    )
    (net (code "4") (name "22") (class "Default")
      (node (ref "C37") (pin "1") (pinfunction "1_1") (pintype "unspecified"))
      (node (ref "R10") (pin "2") (pinfunction "2_2") (pintype "input"))
      (node (ref "R14") (pin "1") (pinfunction "1_1") (pintype "input"))
      (node (ref "U13") (pin "1") (pinfunction "1_1") (pintype "input"))
    )
    (net (code "5") (name "33") (class "Default")
      (node (ref "C38") (pin "1") (pinfunction "1_1") (pintype "unspecified"))
      (node (ref "R11") (pin "2") (pinfunction "2_2") (pintype "input"))
      (node (ref "R15") (pin "1") (pinfunction "1_1") (pintype "input"))
      (node (ref "U14") (pin "1") (pinfunction "1_1") (pintype "input"))
    )
    (net (code "6") (name "44") (class "Default")
      (node (ref "C39") (pin "1") (pinfunction "1_1") (pintype "unspecified"))
      (node (ref "R12") (pin "2") (pinfunction "2_2") (pintype "input"))
      (node (ref "R16") (pin "1") (pinfunction "1_1") (pintype "input"))
      (node (ref "U15") (pin "1") (pinfunction "1_1") (pintype "input"))
    )
    (net (code "7") (name "AD7") (class "Default")
      (node (ref "C1") (pin "2") (pinfunction "2_2") (pintype "unspecified"))
      (node (ref "CH2") (pin "1") (pinfunction "1_1") (pintype "unspecified"))
      (node (ref "R22") (pin "1") (pinfunction "1_1") (pintype "input"))
      (node (ref "R23") (pin "1") (pinfunction "1_1") (pintype "input"))
    )
    (net (code "8") (name "AGND") (class "Default")
      (node (ref "C34") (pin "1") (pinfunction "1_1") (pintype "unspecified"))
      (node (ref "C35") (pin "1") (pinfunction "1_1") (pintype "unspecified"))
      (node (ref "R44") (pin "2") (pinfunction "2_2") (pintype "input"))
      (node (ref "R45") (pin "2") (pinfunction "2_2") (pintype "input"))
      (node (ref "R55") (pin "1") (pinfunction "1_1") (pintype "unspecified"))
      (node (ref "R56") (pin "1") (pinfunction "1_1") (pintype "unspecified"))
      (node (ref "U11") (pin "3") (pinfunction "GND_3") (pintype "unspecified"))
      (node (ref "U8") (pin "56") (pinfunction "56_56") (pintype "unspecified"))
      (node (ref "USB1") (pin "1") (pinfunction "GND_1") (pintype "unspecified"))
      (node (ref "USB1") (pin "12") (pinfunction "GND_12") (pintype "unspecified"))
    )
    (net (code "9") (name "BGND") (class "Default")
      (node (ref "R52") (pin "1") (pinfunction "1_1") (pintype "unspecified"))
      (node (ref "U10") (pin "3") (pinfunction "3_3") (pintype "unspecified"))
      (node (ref "U10") (pin "4") (pinfunction "4_4") (pintype "unspecified"))
    )
    (net (code "10") (name "CGND") (class "Default")
      (node (ref "H1") (pin "5") (pinfunction "5_5") (pintype "unspecified"))
      (node (ref "H1") (pin "6") (pinfunction "6_6") (pintype "unspecified"))
      (node (ref "R53") (pin "1") (pinfunction "1_1") (pintype "unspecified"))
    )
    (net (code "11") (name "DGND") (class "Default")
      (node (ref "CH1") (pin "30") (pinfunction "30_30") (pintype "unspecified"))
      (node (ref "左编码器") (pin "1") (pinfunction "1_1") (pintype "unspecified"))
    )
    (net (code "12") (name "FGND") (class "Default")
      (node (ref "R50") (pin "1") (pinfunction "1_1") (pintype "unspecified"))
      (node (ref "舵机1") (pin "3") (pinfunction "3_3") (pintype "unspecified"))
    )
    (net (code "13") (name "GGND") (class "Default")
      (node (ref "Q1") (pin "2") (pinfunction "2_2") (pintype "input"))
      (node (ref "R17") (pin "1") (pinfunction "1_1") (pintype "unspecified"))
      (node (ref "R27") (pin "1") (pinfunction "1_1") (pintype "input"))
      (node (ref "R54") (pin "1") (pinfunction "1_1") (pintype "unspecified"))
    )
    (net (code "14") (name "GND") (class "Default")
      (node (ref "C1") (pin "1") (pinfunction "1_1") (pintype "unspecified"))
      (node (ref "C10") (pin "1") (pinfunction "1_1") (pintype "unspecified"))
      (node (ref "C11") (pin "1") (pinfunction "1_1") (pintype "unspecified"))
      (node (ref "C12") (pin "1") (pinfunction "1_1") (pintype "unspecified"))
      (node (ref "C13") (pin "2") (pinfunction "2_2") (pintype "input"))
      (node (ref "C14") (pin "2") (pinfunction "2_2") (pintype "input"))
      (node (ref "C15") (pin "2") (pinfunction "2_2") (pintype "unspecified"))
      (node (ref "C16") (pin "2") (pinfunction "2_2") (pintype "input"))
      (node (ref "C17") (pin "2") (pinfunction "2_2") (pintype "unspecified"))
      (node (ref "C2") (pin "2") (pinfunction "2_2") (pintype "input"))
      (node (ref "C3") (pin "1") (pinfunction "1_1") (pintype "unspecified"))
      (node (ref "C36") (pin "2") (pinfunction "2_2") (pintype "unspecified"))
      (node (ref "C37") (pin "2") (pinfunction "2_2") (pintype "unspecified"))
      (node (ref "C38") (pin "2") (pinfunction "2_2") (pintype "unspecified"))
      (node (ref "C39") (pin "2") (pinfunction "2_2") (pintype "unspecified"))
      (node (ref "C4") (pin "1") (pinfunction "1_1") (pintype "unspecified"))
      (node (ref "C5") (pin "1") (pinfunction "1_1") (pintype "unspecified"))
      (node (ref "C6") (pin "1") (pinfunction "1_1") (pintype "unspecified"))
      (node (ref "C7") (pin "2") (pinfunction "2_2") (pintype "input"))
      (node (ref "C8") (pin "2") (pinfunction "2_2") (pintype "input"))
      (node (ref "C9") (pin "1") (pinfunction "1_1") (pintype "unspecified"))
      (node (ref "CH1") (pin "19") (pinfunction "19_19") (pintype "unspecified"))
      (node (ref "CH1") (pin "20") (pinfunction "20_20") (pintype "unspecified"))
      (node (ref "CN5") (pin "1") (pinfunction "-_1") (pintype "unspecified"))
      (node (ref "CN5") (pin "3") (pinfunction "3_3") (pintype "unspecified"))
      (node (ref "CN5") (pin "4") (pinfunction "4_4") (pintype "unspecified"))
      (node (ref "CN6") (pin "1") (pinfunction "-_1") (pintype "unspecified"))
      (node (ref "CN6") (pin "3") (pinfunction "3_3") (pintype "unspecified"))
      (node (ref "CN6") (pin "4") (pinfunction "4_4") (pintype "unspecified"))
      (node (ref "LED1") (pin "1") (pinfunction "K_1") (pintype "input"))
      (node (ref "LED2") (pin "1") (pinfunction "K_1") (pintype "input"))
      (node (ref "LED3") (pin "1") (pinfunction "-_1") (pintype "input"))
      (node (ref "R17") (pin "2") (pinfunction "2_2") (pintype "unspecified"))
      (node (ref "R23") (pin "2") (pinfunction "2_2") (pintype "input"))
      (node (ref "R28") (pin "1") (pinfunction "1_1") (pintype "input"))
      (node (ref "R31") (pin "1") (pinfunction "1_1") (pintype "input"))
      (node (ref "R35") (pin "1") (pinfunction "1_1") (pintype "input"))
      (node (ref "R37") (pin "1") (pinfunction "1_1") (pintype "input"))
      (node (ref "R41") (pin "1") (pinfunction "1_1") (pintype "input"))
      (node (ref "R49") (pin "2") (pinfunction "2_2") (pintype "unspecified"))
      (node (ref "R50") (pin "2") (pinfunction "2_2") (pintype "unspecified"))
      (node (ref "R52") (pin "2") (pinfunction "2_2") (pintype "unspecified"))
      (node (ref "R53") (pin "2") (pinfunction "2_2") (pintype "unspecified"))
      (node (ref "R54") (pin "2") (pinfunction "2_2") (pintype "unspecified"))
      (node (ref "R55") (pin "2") (pinfunction "2_2") (pintype "unspecified"))
      (node (ref "R56") (pin "2") (pinfunction "2_2") (pintype "unspecified"))
      (node (ref "S1") (pin "3") (pinfunction "B2_3") (pintype "input"))
      (node (ref "S1") (pin "4") (pinfunction "B1_4") (pintype "input"))
      (node (ref "U1") (pin "7") (pinfunction "GND_7") (pintype "unspecified"))
      (node (ref "U1") (pin "9") (pinfunction "EP_9") (pintype "unspecified"))
      (node (ref "U12") (pin "2") (pinfunction "2_2") (pintype "input"))
      (node (ref "U13") (pin "2") (pinfunction "2_2") (pintype "input"))
      (node (ref "U14") (pin "2") (pinfunction "2_2") (pintype "input"))
      (node (ref "U15") (pin "2") (pinfunction "2_2") (pintype "input"))
      (node (ref "U2") (pin "7") (pinfunction "GND_7") (pintype "unspecified"))
      (node (ref "U2") (pin "9") (pinfunction "EP_9") (pintype "unspecified"))
      (node (ref "U3") (pin "2") (pinfunction "GND_2") (pintype "unspecified"))
      (node (ref "U8") (pin "55") (pinfunction "55_55") (pintype "unspecified"))
      (node (ref "USB1") (pin "13") (pinfunction "SHELL_13") (pintype "unspecified"))
      (node (ref "USB1") (pin "14") (pinfunction "SHELL_14") (pintype "unspecified"))
      (node (ref "屏幕1") (pin "15") (pinfunction "15_15") (pintype "unspecified"))
      (node (ref "陀螺仪1") (pin "5") (pinfunction "5_5") (pintype "unspecified"))
    )
    (net (code "15") (name "GPIO12") (class "Default")
      (node (ref "R26") (pin "1") (pinfunction "1_1") (pintype "input"))
      (node (ref "R27") (pin "2") (pinfunction "2_2") (pintype "input"))
      (node (ref "U8") (pin "25") (pinfunction "25_25") (pintype "unspecified"))
    )
    (net (code "16") (name "GPIO13") (class "Default")
      (node (ref "R16") (pin "2") (pinfunction "2_2") (pintype "input"))
      (node (ref "U8") (pin "26") (pinfunction "26_26") (pintype "unspecified"))
    )
    (net (code "17") (name "GPIO14") (class "Default")
      (node (ref "R15") (pin "2") (pinfunction "2_2") (pintype "input"))
      (node (ref "U8") (pin "27") (pinfunction "27_27") (pintype "unspecified"))
    )
    (net (code "18") (name "GPIO15") (class "Default")
      (node (ref "R14") (pin "2") (pinfunction "2_2") (pintype "input"))
      (node (ref "U8") (pin "28") (pinfunction "28_28") (pintype "unspecified"))
    )
    (net (code "19") (name "GPIO16") (class "Default")
      (node (ref "R13") (pin "2") (pinfunction "2_2") (pintype "input"))
      (node (ref "U8") (pin "29") (pinfunction "29_29") (pintype "unspecified"))
    )
    (net (code "20") (name "GPIO20") (class "Default")
      (node (ref "R5") (pin "2") (pinfunction "2_2") (pintype "input"))
      (node (ref "U8") (pin "34") (pinfunction "34_34") (pintype "unspecified"))
    )
    (net (code "21") (name "GPIO21") (class "Default")
      (node (ref "R6") (pin "2") (pinfunction "2_2") (pintype "input"))
      (node (ref "U8") (pin "35") (pinfunction "35_35") (pintype "unspecified"))
    )
    (net (code "22") (name "GPIO22") (class "Default")
      (node (ref "R47") (pin "1") (pinfunction "1_1") (pintype "input"))
      (node (ref "U8") (pin "36") (pinfunction "36_36") (pintype "unspecified"))
      (node (ref "陀螺仪1") (pin "4") (pinfunction "4_4") (pintype "unspecified"))
    )
    (net (code "23") (name "GPIO23") (class "Default")
      (node (ref "R48") (pin "1") (pinfunction "1_1") (pintype "input"))
      (node (ref "U8") (pin "37") (pinfunction "37_37") (pintype "unspecified"))
      (node (ref "陀螺仪1") (pin "3") (pinfunction "3_3") (pintype "unspecified"))
    )
    (net (code "24") (name "GPIO24") (class "Default")
      (node (ref "U8") (pin "38") (pinfunction "38_38") (pintype "unspecified"))
      (node (ref "陀螺仪1") (pin "2") (pinfunction "2_2") (pintype "unspecified"))
    )
    (net (code "25") (name "GPIO25") (class "Default")
      (node (ref "U8") (pin "39") (pinfunction "39_39") (pintype "unspecified"))
      (node (ref "陀螺仪1") (pin "1") (pinfunction "1_1") (pintype "unspecified"))
    )
    (net (code "26") (name "GPIO26") (class "Default")
      (node (ref "U8") (pin "40") (pinfunction "40_40") (pintype "unspecified"))
      (node (ref "屏幕1") (pin "5") (pinfunction "5_5") (pintype "unspecified"))
    )
    (net (code "27") (name "GPIO50") (class "Default")
      (node (ref "CH1") (pin "16") (pinfunction "16_16") (pintype "unspecified"))
      (node (ref "右编码器") (pin "4") (pinfunction "4_4") (pintype "unspecified"))
    )
    (net (code "28") (name "GPIO51") (class "Default")
      (node (ref "CH1") (pin "18") (pinfunction "18_18") (pintype "unspecified"))
      (node (ref "左编码器") (pin "4") (pinfunction "4_4") (pintype "unspecified"))
    )
    (net (code "29") (name "GPIO60") (class "Default")
      (node (ref "CH1") (pin "21") (pinfunction "21_21") (pintype "unspecified"))
      (node (ref "屏幕1") (pin "11") (pinfunction "11_11") (pintype "unspecified"))
    )
    (net (code "30") (name "GPIO62") (class "Default")
      (node (ref "CH1") (pin "27") (pinfunction "27_27") (pintype "unspecified"))
      (node (ref "屏幕1") (pin "9") (pinfunction "9_9") (pintype "unspecified"))
    )
    (net (code "31") (name "GPIO63") (class "Default")
      (node (ref "CH1") (pin "23") (pinfunction "23_23") (pintype "unspecified"))
      (node (ref "屏幕1") (pin "3") (pinfunction "3_3") (pintype "unspecified"))
    )
    (net (code "32") (name "GPIO64") (class "Default")
      (node (ref "CH1") (pin "22") (pinfunction "22_22") (pintype "unspecified"))
      (node (ref "左编码器") (pin "3") (pinfunction "3_3") (pintype "unspecified"))
    )
    (net (code "33") (name "GPIO65") (class "Default")
      (node (ref "R3") (pin "1") (pinfunction "1_1") (pintype "input"))
      (node (ref "U10") (pin "1") (pinfunction "1_1") (pintype "unspecified"))
    )
    (net (code "34") (name "GPIO66") (class "Default")
      (node (ref "R4") (pin "1") (pinfunction "1_1") (pintype "input"))
      (node (ref "U10") (pin "2") (pinfunction "2_2") (pintype "unspecified"))
    )
    (net (code "35") (name "GPIO67") (class "Default")
      (node (ref "CH1") (pin "24") (pinfunction "24_24") (pintype "unspecified"))
      (node (ref "右编码器") (pin "3") (pinfunction "3_3") (pintype "unspecified"))
    )
    (net (code "36") (name "GPIO72") (class "Default")
      (node (ref "R2") (pin "1") (pinfunction "1_1") (pintype "input"))
      (node (ref "U10") (pin "6") (pinfunction "6_6") (pintype "unspecified"))
    )
    (net (code "37") (name "GPIO73") (class "Default")
      (node (ref "R1") (pin "1") (pinfunction "1_1") (pintype "input"))
      (node (ref "U10") (pin "5") (pinfunction "5_5") (pintype "unspecified"))
    )
    (net (code "38") (name "GPIO74") (class "Default")
      (node (ref "CH1") (pin "14") (pinfunction "14_14") (pintype "unspecified"))
      (node (ref "屏幕1") (pin "7") (pinfunction "7_7") (pintype "unspecified"))
    )
    (net (code "39") (name "GPIO75") (class "Default")
      (node (ref "CH1") (pin "12") (pinfunction "12_12") (pintype "unspecified"))
      (node (ref "屏幕1") (pin "1") (pinfunction "1_1") (pintype "unspecified"))
    )
    (net (code "40") (name "GPIO86") (class "Default")
      (node (ref "R24") (pin "2") (pinfunction "2_2") (pintype "input"))
      (node (ref "U8") (pin "49") (pinfunction "49_49") (pintype "unspecified"))
    )
    (net (code "41") (name "GPIO88") (class "Default")
      (node (ref "CH1") (pin "4") (pinfunction "4_4") (pintype "unspecified"))
      (node (ref "R29") (pin "2") (pinfunction "2_2") (pintype "input"))
    )
    (net (code "42") (name "GPIO89") (class "Default")
      (node (ref "CH1") (pin "6") (pinfunction "6_6") (pintype "unspecified"))
      (node (ref "R30") (pin "2") (pinfunction "2_2") (pintype "input"))
    )
    (net (code "43") (name "HGND") (class "Default")
      (node (ref "R49") (pin "1") (pinfunction "1_1") (pintype "unspecified"))
      (node (ref "U9") (pin "1") (pinfunction "1_1") (pintype "unspecified"))
      (node (ref "U9") (pin "2") (pinfunction "2_2") (pintype "unspecified"))
    )
    (net (code "44") (name "IGND") (class "Default")
      (node (ref "CH1") (pin "2") (pinfunction "2_2") (pintype "unspecified"))
      (node (ref "右编码器") (pin "1") (pinfunction "1_1") (pintype "unspecified"))
    )
    (net (code "45") (name "Net-(BUZZER1-+)") (class "Default")
      (node (ref "BUZZER1") (pin "1") (pinfunction "+_1") (pintype "unspecified"))
      (node (ref "R25") (pin "2") (pinfunction "2_2") (pintype "input"))
    )
    (net (code "46") (name "Net-(BUZZER1--)") (class "Default")
      (node (ref "BUZZER1") (pin "2") (pinfunction "-_2") (pintype "unspecified"))
      (node (ref "Q1") (pin "3") (pinfunction "3_3") (pintype "input"))
    )
    (net (code "47") (name "Net-(C5-Pad2)") (class "Default")
      (node (ref "C5") (pin "2") (pinfunction "2_2") (pintype "unspecified"))
      (node (ref "R32") (pin "1") (pinfunction "1_1") (pintype "input"))
    )
    (net (code "48") (name "Net-(C11-Pad2)") (class "Default")
      (node (ref "C11") (pin "2") (pinfunction "2_2") (pintype "unspecified"))
      (node (ref "R38") (pin "1") (pinfunction "1_1") (pintype "input"))
    )
    (net (code "49") (name "Net-(CH1-Pad8)") (class "Default")
      (node (ref "CH1") (pin "8") (pinfunction "8_8") (pintype "unspecified"))
      (node (ref "R1") (pin "2") (pinfunction "2_2") (pintype "input"))
    )
    (net (code "50") (name "Net-(CH1-Pad10)") (class "Default")
      (node (ref "CH1") (pin "10") (pinfunction "10_10") (pintype "unspecified"))
      (node (ref "R2") (pin "2") (pinfunction "2_2") (pintype "input"))
    )
    (net (code "51") (name "Net-(CH1-Pad26)") (class "Default")
      (node (ref "CH1") (pin "26") (pinfunction "26_26") (pintype "unspecified"))
      (node (ref "R3") (pin "2") (pinfunction "2_2") (pintype "input"))
    )
    (net (code "52") (name "Net-(CH1-Pad28)") (class "Default")
      (node (ref "CH1") (pin "28") (pinfunction "28_28") (pintype "unspecified"))
      (node (ref "R4") (pin "2") (pinfunction "2_2") (pintype "input"))
    )
    (net (code "53") (name "Net-(CN5-+)") (class "Default")
      (node (ref "CN5") (pin "2") (pinfunction "+_2") (pintype "unspecified"))
      (node (ref "D1") (pin "1") (pinfunction "K_1") (pintype "unspecified"))
      (node (ref "Q2") (pin "3") (pinfunction "S_3") (pintype "unspecified"))
      (node (ref "SW1") (pin "3") (pinfunction "3_3") (pintype "unspecified"))
    )
    (net (code "54") (name "Net-(D1-A)") (class "Default")
      (node (ref "D1") (pin "2") (pinfunction "A_2") (pintype "unspecified"))
      (node (ref "R28") (pin "2") (pinfunction "2_2") (pintype "input"))
      (node (ref "SW1") (pin "1") (pinfunction "1_1") (pintype "unspecified"))
    )
    (net (code "55") (name "Net-(D2-A)") (class "Default")
      (node (ref "C6") (pin "2") (pinfunction "2_2") (pintype "unspecified"))
      (node (ref "C7") (pin "1") (pinfunction "1_1") (pintype "input"))
      (node (ref "D2") (pin "1") (pinfunction "A_1") (pintype "unspecified"))
      (node (ref "L1") (pin "2") (pinfunction "2_2") (pintype "unspecified"))
    )
    (net (code "56") (name "Net-(D3-K)") (class "Default")
      (node (ref "C2") (pin "1") (pinfunction "1_1") (pintype "input"))
      (node (ref "C3") (pin "2") (pinfunction "2_2") (pintype "unspecified"))
      (node (ref "C4") (pin "2") (pinfunction "2_2") (pintype "unspecified"))
      (node (ref "D3") (pin "2") (pinfunction "K_2") (pintype "unspecified"))
      (node (ref "U1") (pin "2") (pinfunction "VIN_2") (pintype "unspecified"))
      (node (ref "U1") (pin "3") (pinfunction "EN_3") (pintype "unspecified"))
    )
    (net (code "57") (name "Net-(LED1-A)") (class "Default")
      (node (ref "LED1") (pin "2") (pinfunction "A_2") (pintype "input"))
      (node (ref "R43") (pin "2") (pinfunction "2_2") (pintype "input"))
    )
    (net (code "58") (name "Net-(LED2-A)") (class "Default")
      (node (ref "LED2") (pin "2") (pinfunction "A_2") (pintype "input"))
      (node (ref "R36") (pin "1") (pinfunction "1_1") (pintype "input"))
    )
    (net (code "59") (name "Net-(LED3-+)") (class "Default")
      (node (ref "LED3") (pin "2") (pinfunction "+_2") (pintype "input"))
      (node (ref "R42") (pin "1") (pinfunction "1_1") (pintype "input"))
    )
    (net (code "60") (name "Net-(Q1-Pad1)") (class "Default")
      (node (ref "Q1") (pin "1") (pinfunction "1_1") (pintype "input"))
      (node (ref "R26") (pin "2") (pinfunction "2_2") (pintype "input"))
    )
    (net (code "61") (name "Net-(Q2-G)") (class "Default")
      (node (ref "Q2") (pin "1") (pinfunction "G_1") (pintype "unspecified"))
      (node (ref "SW1") (pin "2") (pinfunction "2_2") (pintype "unspecified"))
    )
    (net (code "62") (name "Net-(R24-Pad1)") (class "Default")
      (node (ref "R24") (pin "1") (pinfunction "1_1") (pintype "input"))
      (node (ref "舵机1") (pin "1") (pinfunction "1_1") (pintype "unspecified"))
    )
    (net (code "63") (name "Net-(R29-Pad1)") (class "Default")
      (node (ref "R29") (pin "1") (pinfunction "1_1") (pintype "input"))
      (node (ref "U9") (pin "5") (pinfunction "5_5") (pintype "unspecified"))
    )
    (net (code "64") (name "Net-(R30-Pad1)") (class "Default")
      (node (ref "R30") (pin "1") (pinfunction "1_1") (pintype "input"))
      (node (ref "U9") (pin "6") (pinfunction "6_6") (pintype "unspecified"))
    )
    (net (code "65") (name "Net-(R33-Pad1)") (class "Default")
      (node (ref "R33") (pin "1") (pinfunction "1_1") (pintype "input"))
      (node (ref "R34") (pin "2") (pinfunction "2_2") (pintype "input"))
    )
    (net (code "66") (name "Net-(R39-Pad1)") (class "Default")
      (node (ref "R39") (pin "1") (pinfunction "1_1") (pintype "input"))
      (node (ref "R40") (pin "2") (pinfunction "2_2") (pintype "input"))
    )
    (net (code "67") (name "Net-(S1-A1)") (class "Default")
      (node (ref "R5") (pin "1") (pinfunction "1_1") (pintype "input"))
      (node (ref "R7") (pin "2") (pinfunction "2_2") (pintype "input"))
      (node (ref "S1") (pin "1") (pinfunction "A1_1") (pintype "input"))
    )
    (net (code "68") (name "Net-(S1-A2)") (class "Default")
      (node (ref "R6") (pin "1") (pinfunction "1_1") (pintype "input"))
      (node (ref "R8") (pin "2") (pinfunction "2_2") (pintype "input"))
      (node (ref "S1") (pin "2") (pinfunction "A2_2") (pintype "input"))
    )
    (net (code "69") (name "Net-(U1-BOOT)") (class "Default")
      (node (ref "C32") (pin "2") (pinfunction "2_2") (pintype "unspecified"))
      (node (ref "U1") (pin "1") (pinfunction "BOOT_1") (pintype "unspecified"))
    )
    (net (code "70") (name "Net-(U1-COMP)") (class "Default")
      (node (ref "R32") (pin "2") (pinfunction "2_2") (pintype "input"))
      (node (ref "U1") (pin "6") (pinfunction "COMP_6") (pintype "unspecified"))
    )
    (net (code "71") (name "Net-(U1-FB)") (class "Default")
      (node (ref "R34") (pin "1") (pinfunction "1_1") (pintype "input"))
      (node (ref "R35") (pin "2") (pinfunction "2_2") (pintype "input"))
      (node (ref "U1") (pin "5") (pinfunction "FB_5") (pintype "unspecified"))
    )
    (net (code "72") (name "Net-(U1-RT{slash}CLK)") (class "Default")
      (node (ref "R31") (pin "2") (pinfunction "2_2") (pintype "input"))
      (node (ref "U1") (pin "4") (pinfunction "RT/CLK_4") (pintype "unspecified"))
    )
    (net (code "73") (name "Net-(U1-SW)") (class "Default")
      (node (ref "C32") (pin "1") (pinfunction "1_1") (pintype "unspecified"))
      (node (ref "L1") (pin "1") (pinfunction "1_1") (pintype "unspecified"))
      (node (ref "U1") (pin "8") (pinfunction "SW_8") (pintype "unspecified"))
    )
    (net (code "74") (name "Net-(U2-BOOT)") (class "Default")
      (node (ref "C33") (pin "2") (pinfunction "2_2") (pintype "unspecified"))
      (node (ref "U2") (pin "1") (pinfunction "BOOT_1") (pintype "unspecified"))
    )
    (net (code "75") (name "Net-(U2-COMP)") (class "Default")
      (node (ref "R38") (pin "2") (pinfunction "2_2") (pintype "input"))
      (node (ref "U2") (pin "6") (pinfunction "COMP_6") (pintype "unspecified"))
    )
    (net (code "76") (name "Net-(U2-FB)") (class "Default")
      (node (ref "R40") (pin "1") (pinfunction "1_1") (pintype "input"))
      (node (ref "R41") (pin "2") (pinfunction "2_2") (pintype "input"))
      (node (ref "U2") (pin "5") (pinfunction "FB_5") (pintype "unspecified"))
    )
    (net (code "77") (name "Net-(U2-RT{slash}CLK)") (class "Default")
      (node (ref "R37") (pin "2") (pinfunction "2_2") (pintype "input"))
      (node (ref "U2") (pin "4") (pinfunction "RT/CLK_4") (pintype "unspecified"))
    )
    (net (code "78") (name "Net-(U2-SW)") (class "Default")
      (node (ref "C33") (pin "1") (pinfunction "1_1") (pintype "unspecified"))
      (node (ref "L2") (pin "1") (pinfunction "1_1") (pintype "unspecified"))
      (node (ref "U2") (pin "8") (pinfunction "SW_8") (pintype "unspecified"))
    )
    (net (code "79") (name "Net-(U11-V3)") (class "Default")
      (node (ref "C34") (pin "2") (pinfunction "2_2") (pintype "unspecified"))
      (node (ref "U11") (pin "8") (pinfunction "V3_8") (pintype "unspecified"))
    )
    (net (code "80") (name "Net-(USB1-CC1)") (class "Default")
      (node (ref "R45") (pin "1") (pinfunction "1_1") (pintype "input"))
      (node (ref "USB1") (pin "4") (pinfunction "CC1_4") (pintype "unspecified"))
    )
    (net (code "81") (name "Net-(USB1-CC2)") (class "Default")
      (node (ref "R44") (pin "1") (pinfunction "1_1") (pintype "input"))
      (node (ref "USB1") (pin "10") (pinfunction "CC2_10") (pintype "unspecified"))
    )
    (net (code "82") (name "RX0") (class "Default")
      (node (ref "CH1") (pin "5") (pinfunction "5_5") (pintype "unspecified"))
      (node (ref "H1") (pin "3") (pinfunction "3_3") (pintype "unspecified"))
      (node (ref "U11") (pin "6") (pinfunction "TXD_6") (pintype "unspecified"))
    )
    (net (code "83") (name "TX0") (class "Default")
      (node (ref "CH1") (pin "3") (pinfunction "3_3") (pintype "unspecified"))
      (node (ref "H1") (pin "1") (pinfunction "1_1") (pintype "unspecified"))
      (node (ref "U11") (pin "7") (pinfunction "RXD_7") (pintype "unspecified"))
    )
    (net (code "84") (name "UD+") (class "Default")
      (node (ref "U11") (pin "1") (pinfunction "UD+_1") (pintype "unspecified"))
      (node (ref "USB1") (pin "6") (pinfunction "DP1_6") (pintype "unspecified"))
      (node (ref "USB1") (pin "8") (pinfunction "DP2_8") (pintype "unspecified"))
    )
    (net (code "85") (name "UD-") (class "Default")
      (node (ref "U11") (pin "2") (pinfunction "UD-_2") (pintype "unspecified"))
      (node (ref "USB1") (pin "5") (pinfunction "DN2_5") (pintype "unspecified"))
      (node (ref "USB1") (pin "7") (pinfunction "DN1_7") (pintype "unspecified"))
    )
    (net (code "86") (name "VCCBAT") (class "Default")
      (node (ref "C10") (pin "2") (pinfunction "2_2") (pintype "unspecified"))
      (node (ref "C8") (pin "1") (pinfunction "1_1") (pintype "input"))
      (node (ref "C9") (pin "2") (pinfunction "2_2") (pintype "unspecified"))
      (node (ref "CN6") (pin "2") (pinfunction "+_2") (pintype "unspecified"))
      (node (ref "D3") (pin "1") (pinfunction "A_1") (pintype "unspecified"))
      (node (ref "Q2") (pin "2") (pinfunction "D_2") (pintype "unspecified"))
      (node (ref "R22") (pin "2") (pinfunction "2_2") (pintype "input"))
      (node (ref "U2") (pin "2") (pinfunction "VIN_2") (pintype "unspecified"))
      (node (ref "U2") (pin "3") (pinfunction "EN_3") (pintype "unspecified"))
    )
    (net (code "87") (name "VCCSERVO") (class "Default")
      (node (ref "C12") (pin "2") (pinfunction "2_2") (pintype "unspecified"))
      (node (ref "C13") (pin "1") (pinfunction "1_1") (pintype "input"))
      (node (ref "L2") (pin "2") (pinfunction "2_2") (pintype "unspecified"))
      (node (ref "R39") (pin "2") (pinfunction "2_2") (pintype "input"))
      (node (ref "R42") (pin "2") (pinfunction "2_2") (pintype "input"))
      (node (ref "舵机1") (pin "2") (pinfunction "2_2") (pintype "unspecified"))
    )
    (net (code "88") (name "unconnected-(CH1-Pad1)") (class "Default")
      (node (ref "CH1") (pin "1") (pinfunction "1_1") (pintype "unspecified+no_connect"))
    )
    (net (code "89") (name "unconnected-(CH1-Pad7)") (class "Default")
      (node (ref "CH1") (pin "7") (pinfunction "7_7") (pintype "unspecified+no_connect"))
    )
    (net (code "90") (name "unconnected-(CH1-Pad9)") (class "Default")
      (node (ref "CH1") (pin "9") (pinfunction "9_9") (pintype "unspecified+no_connect"))
    )
    (net (code "91") (name "unconnected-(CH1-Pad11)") (class "Default")
      (node (ref "CH1") (pin "11") (pinfunction "11_11") (pintype "unspecified+no_connect"))
    )
    (net (code "92") (name "unconnected-(CH1-Pad13)") (class "Default")
      (node (ref "CH1") (pin "13") (pinfunction "13_13") (pintype "unspecified+no_connect"))
    )
    (net (code "93") (name "unconnected-(CH1-Pad15)") (class "Default")
      (node (ref "CH1") (pin "15") (pinfunction "15_15") (pintype "unspecified+no_connect"))
    )
    (net (code "94") (name "unconnected-(CH1-Pad17)") (class "Default")
      (node (ref "CH1") (pin "17") (pinfunction "17_17") (pintype "unspecified+no_connect"))
    )
    (net (code "95") (name "unconnected-(CH1-Pad25)") (class "Default")
      (node (ref "CH1") (pin "25") (pinfunction "25_25") (pintype "unspecified+no_connect"))
    )
    (net (code "96") (name "unconnected-(CH2-Pad2)") (class "Default")
      (node (ref "CH2") (pin "2") (pinfunction "2_2") (pintype "unspecified+no_connect"))
    )
    (net (code "97") (name "unconnected-(CH2-Pad3)") (class "Default")
      (node (ref "CH2") (pin "3") (pinfunction "3_3") (pintype "unspecified+no_connect"))
    )
    (net (code "98") (name "unconnected-(CH2-Pad4)") (class "Default")
      (node (ref "CH2") (pin "4") (pinfunction "4_4") (pintype "unspecified+no_connect"))
    )
    (net (code "99") (name "unconnected-(CH2-Pad5)") (class "Default")
      (node (ref "CH2") (pin "5") (pinfunction "5_5") (pintype "unspecified+no_connect"))
    )
    (net (code "100") (name "unconnected-(CH2-Pad6)") (class "Default")
      (node (ref "CH2") (pin "6") (pinfunction "6_6") (pintype "unspecified+no_connect"))
    )
    (net (code "101") (name "unconnected-(CH2-Pad7)") (class "Default")
      (node (ref "CH2") (pin "7") (pinfunction "7_7") (pintype "unspecified+no_connect"))
    )
    (net (code "102") (name "unconnected-(CH2-Pad8)") (class "Default")
      (node (ref "CH2") (pin "8") (pinfunction "8_8") (pintype "unspecified+no_connect"))
    )
    (net (code "103") (name "unconnected-(CH2-Pad9)") (class "Default")
      (node (ref "CH2") (pin "9") (pinfunction "9_9") (pintype "unspecified+no_connect"))
    )
    (net (code "104") (name "unconnected-(CH2-Pad10)") (class "Default")
      (node (ref "CH2") (pin "10") (pinfunction "10_10") (pintype "unspecified+no_connect"))
    )
    (net (code "105") (name "unconnected-(H1-Pad2)") (class "Default")
      (node (ref "H1") (pin "2") (pinfunction "2_2") (pintype "unspecified+no_connect"))
    )
    (net (code "106") (name "unconnected-(H1-Pad4)") (class "Default")
      (node (ref "H1") (pin "4") (pinfunction "4_4") (pintype "unspecified+no_connect"))
    )
    (net (code "107") (name "unconnected-(H1-Pad8)") (class "Default")
      (node (ref "H1") (pin "8") (pinfunction "8_8") (pintype "unspecified+no_connect"))
    )
    (net (code "108") (name "unconnected-(U3-NC-Pad4)") (class "Default")
      (node (ref "U3") (pin "4") (pinfunction "NC_4") (pintype "unspecified+no_connect"))
    )
    (net (code "109") (name "unconnected-(U8-Pad1)") (class "Default")
      (node (ref "U8") (pin "1") (pinfunction "1_1") (pintype "unspecified+no_connect"))
    )
    (net (code "110") (name "unconnected-(U8-Pad2)") (class "Default")
      (node (ref "U8") (pin "2") (pinfunction "2_2") (pintype "unspecified+no_connect"))
    )
    (net (code "111") (name "unconnected-(U8-Pad3)") (class "Default")
      (node (ref "U8") (pin "3") (pinfunction "3_3") (pintype "unspecified+no_connect"))
    )
    (net (code "112") (name "unconnected-(U8-Pad4)") (class "Default")
      (node (ref "U8") (pin "4") (pinfunction "4_4") (pintype "unspecified+no_connect"))
    )
    (net (code "113") (name "unconnected-(U8-Pad5)") (class "Default")
      (node (ref "U8") (pin "5") (pinfunction "5_5") (pintype "unspecified+no_connect"))
    )
    (net (code "114") (name "unconnected-(U8-Pad6)") (class "Default")
      (node (ref "U8") (pin "6") (pinfunction "6_6") (pintype "unspecified+no_connect"))
    )
    (net (code "115") (name "unconnected-(U8-Pad7)") (class "Default")
      (node (ref "U8") (pin "7") (pinfunction "7_7") (pintype "unspecified+no_connect"))
    )
    (net (code "116") (name "unconnected-(U8-Pad8)") (class "Default")
      (node (ref "U8") (pin "8") (pinfunction "8_8") (pintype "unspecified+no_connect"))
    )
    (net (code "117") (name "unconnected-(U8-Pad9)") (class "Default")
      (node (ref "U8") (pin "9") (pinfunction "9_9") (pintype "unspecified+no_connect"))
    )
    (net (code "118") (name "unconnected-(U8-Pad10)") (class "Default")
      (node (ref "U8") (pin "10") (pinfunction "10_10") (pintype "unspecified+no_connect"))
    )
    (net (code "119") (name "unconnected-(U8-Pad11)") (class "Default")
      (node (ref "U8") (pin "11") (pinfunction "11_11") (pintype "unspecified+no_connect"))
    )
    (net (code "120") (name "unconnected-(U8-Pad12)") (class "Default")
      (node (ref "U8") (pin "12") (pinfunction "12_12") (pintype "unspecified+no_connect"))
    )
    (net (code "121") (name "unconnected-(U8-Pad13)") (class "Default")
      (node (ref "U8") (pin "13") (pinfunction "13_13") (pintype "unspecified+no_connect"))
    )
    (net (code "122") (name "unconnected-(U8-Pad14)") (class "Default")
      (node (ref "U8") (pin "14") (pinfunction "14_14") (pintype "unspecified+no_connect"))
    )
    (net (code "123") (name "unconnected-(U8-Pad15)") (class "Default")
      (node (ref "U8") (pin "15") (pinfunction "15_15") (pintype "unspecified+no_connect"))
    )
    (net (code "124") (name "unconnected-(U8-Pad16)") (class "Default")
      (node (ref "U8") (pin "16") (pinfunction "16_16") (pintype "unspecified+no_connect"))
    )
    (net (code "125") (name "unconnected-(U8-Pad17)") (class "Default")
      (node (ref "U8") (pin "17") (pinfunction "17_17") (pintype "unspecified+no_connect"))
    )
    (net (code "126") (name "unconnected-(U8-Pad18)") (class "Default")
      (node (ref "U8") (pin "18") (pinfunction "18_18") (pintype "unspecified+no_connect"))
    )
    (net (code "127") (name "unconnected-(U8-Pad19)") (class "Default")
      (node (ref "U8") (pin "19") (pinfunction "19_19") (pintype "unspecified+no_connect"))
    )
    (net (code "128") (name "unconnected-(U8-Pad20)") (class "Default")
      (node (ref "U8") (pin "20") (pinfunction "20_20") (pintype "unspecified+no_connect"))
    )
    (net (code "129") (name "unconnected-(U8-Pad21)") (class "Default")
      (node (ref "U8") (pin "21") (pinfunction "21_21") (pintype "unspecified+no_connect"))
    )
    (net (code "130") (name "unconnected-(U8-Pad22)") (class "Default")
      (node (ref "U8") (pin "22") (pinfunction "22_22") (pintype "unspecified+no_connect"))
    )
    (net (code "131") (name "unconnected-(U8-Pad23)") (class "Default")
      (node (ref "U8") (pin "23") (pinfunction "23_23") (pintype "unspecified+no_connect"))
    )
    (net (code "132") (name "unconnected-(U8-Pad24)") (class "Default")
      (node (ref "U8") (pin "24") (pinfunction "24_24") (pintype "unspecified+no_connect"))
    )
    (net (code "133") (name "unconnected-(U8-Pad30)") (class "Default")
      (node (ref "U8") (pin "30") (pinfunction "30_30") (pintype "unspecified+no_connect"))
    )
    (net (code "134") (name "unconnected-(U8-Pad31)") (class "Default")
      (node (ref "U8") (pin "31") (pinfunction "31_31") (pintype "unspecified+no_connect"))
    )
    (net (code "135") (name "unconnected-(U8-Pad32)") (class "Default")
      (node (ref "U8") (pin "32") (pinfunction "32_32") (pintype "unspecified+no_connect"))
    )
    (net (code "136") (name "unconnected-(U8-Pad33)") (class "Default")
      (node (ref "U8") (pin "33") (pinfunction "33_33") (pintype "unspecified+no_connect"))
    )
    (net (code "137") (name "unconnected-(U8-Pad41)") (class "Default")
      (node (ref "U8") (pin "41") (pinfunction "41_41") (pintype "unspecified+no_connect"))
    )
    (net (code "138") (name "unconnected-(U8-Pad42)") (class "Default")
      (node (ref "U8") (pin "42") (pinfunction "42_42") (pintype "unspecified+no_connect"))
    )
    (net (code "139") (name "unconnected-(U8-Pad43)") (class "Default")
      (node (ref "U8") (pin "43") (pinfunction "43_43") (pintype "unspecified+no_connect"))
    )
    (net (code "140") (name "unconnected-(U8-Pad44)") (class "Default")
      (node (ref "U8") (pin "44") (pinfunction "44_44") (pintype "unspecified+no_connect"))
    )
    (net (code "141") (name "unconnected-(U8-Pad45)") (class "Default")
      (node (ref "U8") (pin "45") (pinfunction "45_45") (pintype "unspecified+no_connect"))
    )
    (net (code "142") (name "unconnected-(U8-Pad46)") (class "Default")
      (node (ref "U8") (pin "46") (pinfunction "46_46") (pintype "unspecified+no_connect"))
    )
    (net (code "143") (name "unconnected-(U8-Pad47)") (class "Default")
      (node (ref "U8") (pin "47") (pinfunction "47_47") (pintype "unspecified+no_connect"))
    )
    (net (code "144") (name "unconnected-(U8-Pad48)") (class "Default")
      (node (ref "U8") (pin "48") (pinfunction "48_48") (pintype "unspecified+no_connect"))
    )
    (net (code "145") (name "unconnected-(U8-Pad50)") (class "Default")
      (node (ref "U8") (pin "50") (pinfunction "50_50") (pintype "unspecified+no_connect"))
    )
    (net (code "146") (name "unconnected-(U8-Pad51)") (class "Default")
      (node (ref "U8") (pin "51") (pinfunction "51_51") (pintype "unspecified+no_connect"))
    )
    (net (code "147") (name "unconnected-(U8-Pad52)") (class "Default")
      (node (ref "U8") (pin "52") (pinfunction "52_52") (pintype "unspecified+no_connect"))
    )
    (net (code "148") (name "unconnected-(U8-Pad53)") (class "Default")
      (node (ref "U8") (pin "53") (pinfunction "53_53") (pintype "unspecified+no_connect"))
    )
    (net (code "149") (name "unconnected-(U8-Pad54)") (class "Default")
      (node (ref "U8") (pin "54") (pinfunction "54_54") (pintype "unspecified+no_connect"))
    )
    (net (code "150") (name "unconnected-(U9-Pad3)") (class "Default")
      (node (ref "U9") (pin "3") (pinfunction "3_3") (pintype "unspecified+no_connect"))
    )
    (net (code "151") (name "unconnected-(U9-Pad4)") (class "Default")
      (node (ref "U9") (pin "4") (pinfunction "4_4") (pintype "unspecified+no_connect"))
    )
    (net (code "152") (name "unconnected-(U11-RTS#-Pad4)") (class "Default")
      (node (ref "U11") (pin "4") (pinfunction "RTS#_4") (pintype "unspecified+no_connect"))
    )
    (net (code "153") (name "unconnected-(USB1-SBU1-Pad9)") (class "Default")
      (node (ref "USB1") (pin "9") (pinfunction "SBU1_9") (pintype "unspecified+no_connect"))
    )
    (net (code "154") (name "unconnected-(USB1-SBU2-Pad3)") (class "Default")
      (node (ref "USB1") (pin "3") (pinfunction "SBU2_3") (pintype "unspecified+no_connect"))
    )
    (net (code "155") (name "unconnected-(USB1-VBUS-Pad2)") (class "Default")
      (node (ref "USB1") (pin "2") (pinfunction "VBUS_2") (pintype "unspecified+no_connect"))
    )
    (net (code "156") (name "unconnected-(USB1-VBUS-Pad11)") (class "Default")
      (node (ref "USB1") (pin "11") (pinfunction "VBUS_11") (pintype "unspecified+no_connect"))
    )
    (net (code "157") (name "unconnected-(右编码器-Pad5)") (class "Default")
      (node (ref "右编码器") (pin "5") (pinfunction "5_5") (pintype "unspecified+no_connect"))
    )
    (net (code "158") (name "unconnected-(右编码器-Pad6)") (class "Default")
      (node (ref "右编码器") (pin "6") (pinfunction "6_6") (pintype "unspecified+no_connect"))
    )
    (net (code "159") (name "unconnected-(屏幕1-Pad2)") (class "Default")
      (node (ref "屏幕1") (pin "2") (pinfunction "2_2") (pintype "unspecified+no_connect"))
    )
    (net (code "160") (name "unconnected-(屏幕1-Pad4)") (class "Default")
      (node (ref "屏幕1") (pin "4") (pinfunction "4_4") (pintype "unspecified+no_connect"))
    )
    (net (code "161") (name "unconnected-(屏幕1-Pad6)") (class "Default")
      (node (ref "屏幕1") (pin "6") (pinfunction "6_6") (pintype "unspecified+no_connect"))
    )
    (net (code "162") (name "unconnected-(屏幕1-Pad8)") (class "Default")
      (node (ref "屏幕1") (pin "8") (pinfunction "8_8") (pintype "unspecified+no_connect"))
    )
    (net (code "163") (name "unconnected-(屏幕1-Pad10)") (class "Default")
      (node (ref "屏幕1") (pin "10") (pinfunction "10_10") (pintype "unspecified+no_connect"))
    )
    (net (code "164") (name "unconnected-(屏幕1-Pad12)") (class "Default")
      (node (ref "屏幕1") (pin "12") (pinfunction "12_12") (pintype "unspecified+no_connect"))
    )
    (net (code "165") (name "unconnected-(屏幕1-Pad14)") (class "Default")
      (node (ref "屏幕1") (pin "14") (pinfunction "14_14") (pintype "unspecified+no_connect"))
    )
    (net (code "166") (name "unconnected-(屏幕1-Pad16)") (class "Default")
      (node (ref "屏幕1") (pin "16") (pinfunction "16_16") (pintype "unspecified+no_connect"))
    )
    (net (code "167") (name "unconnected-(左编码器-Pad5)") (class "Default")
      (node (ref "左编码器") (pin "5") (pinfunction "5_5") (pintype "unspecified+no_connect"))
    )
    (net (code "168") (name "unconnected-(左编码器-Pad6)") (class "Default")
      (node (ref "左编码器") (pin "6") (pinfunction "6_6") (pintype "unspecified+no_connect"))
    )
  )
)
